# BPM.net
KiCad netlist of a schematic drawn in EAGLE
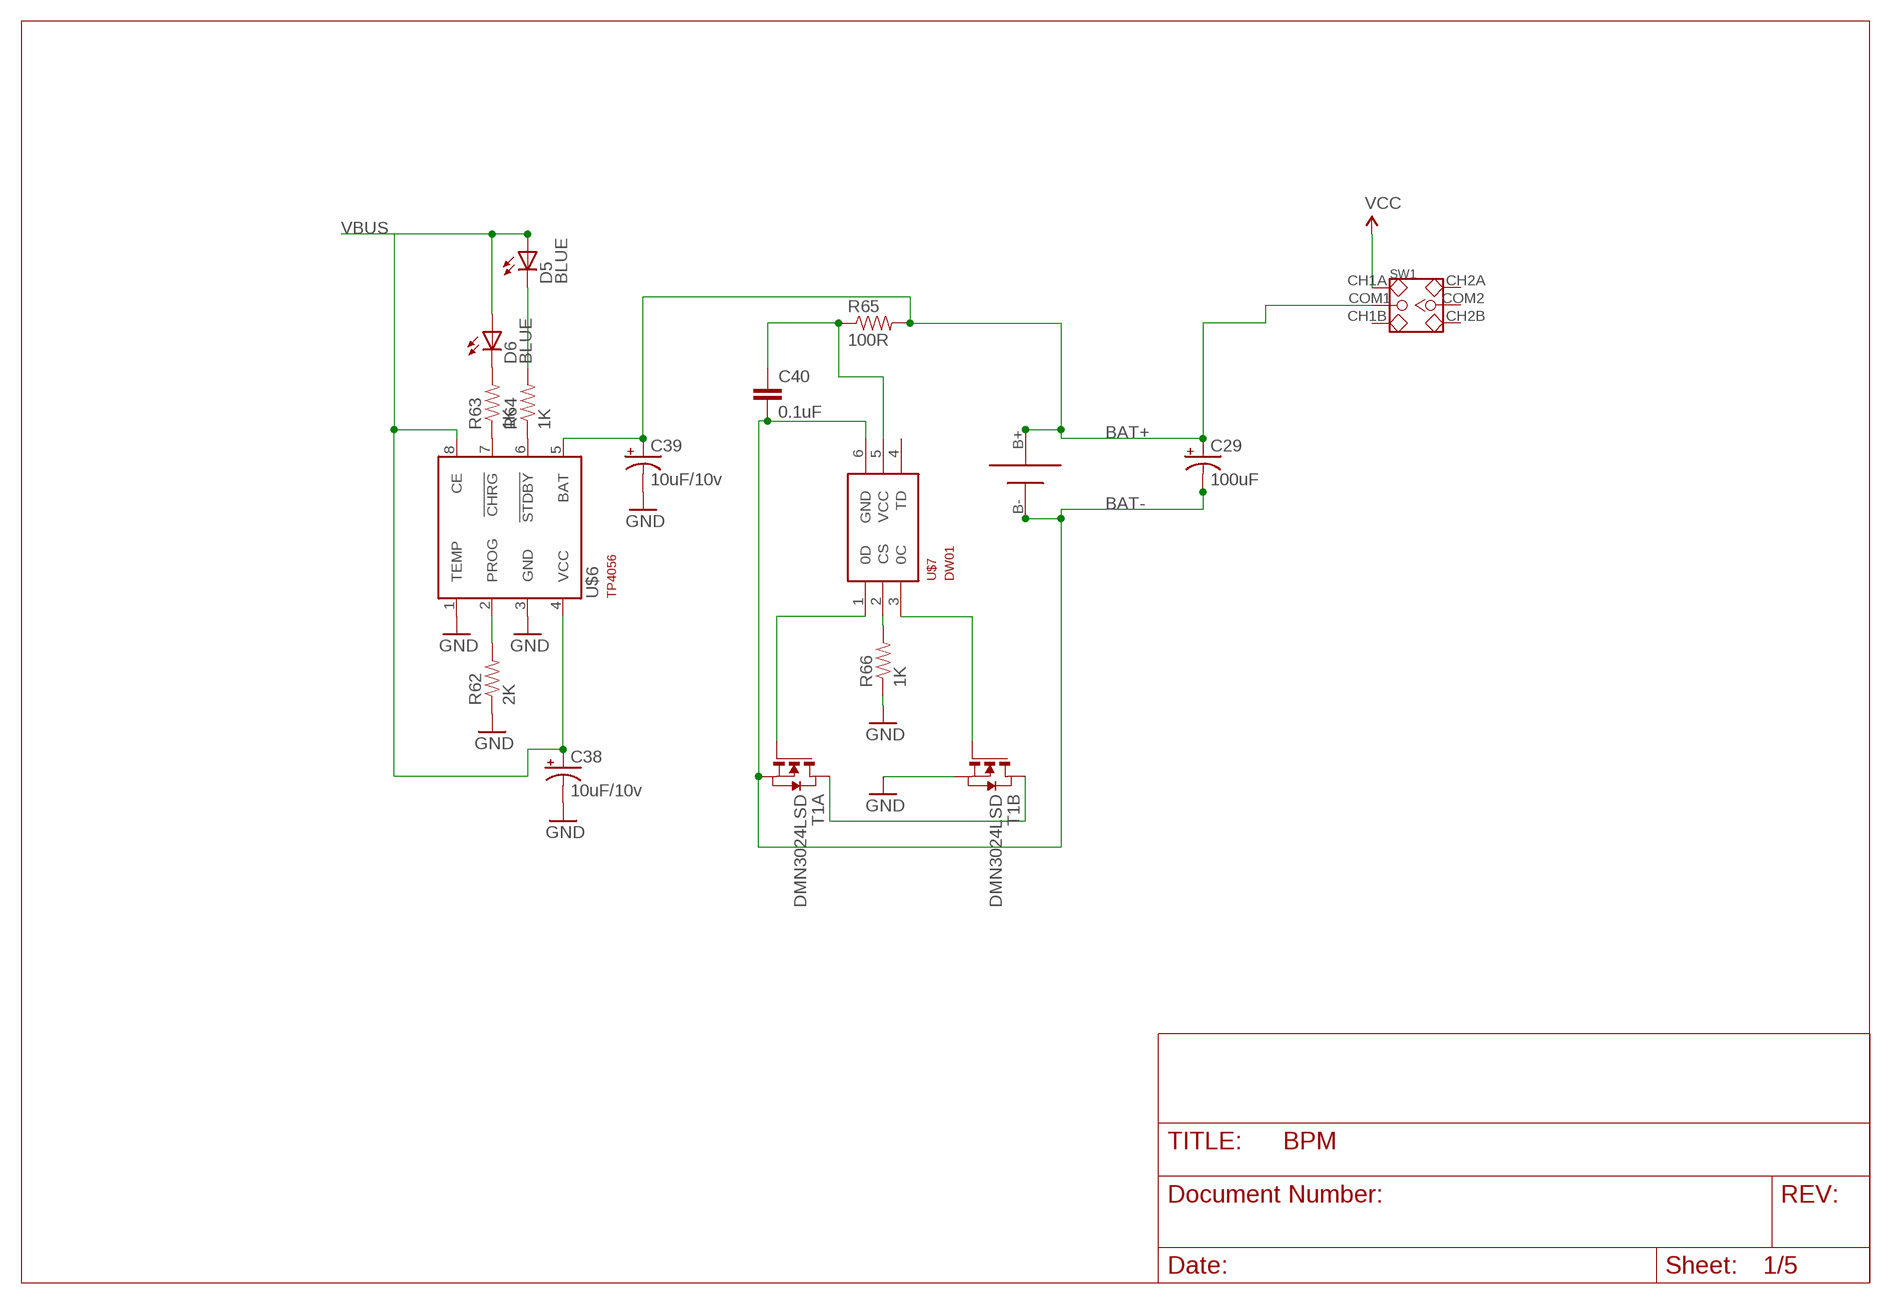
[diagram p0: schematic, sheet 1]
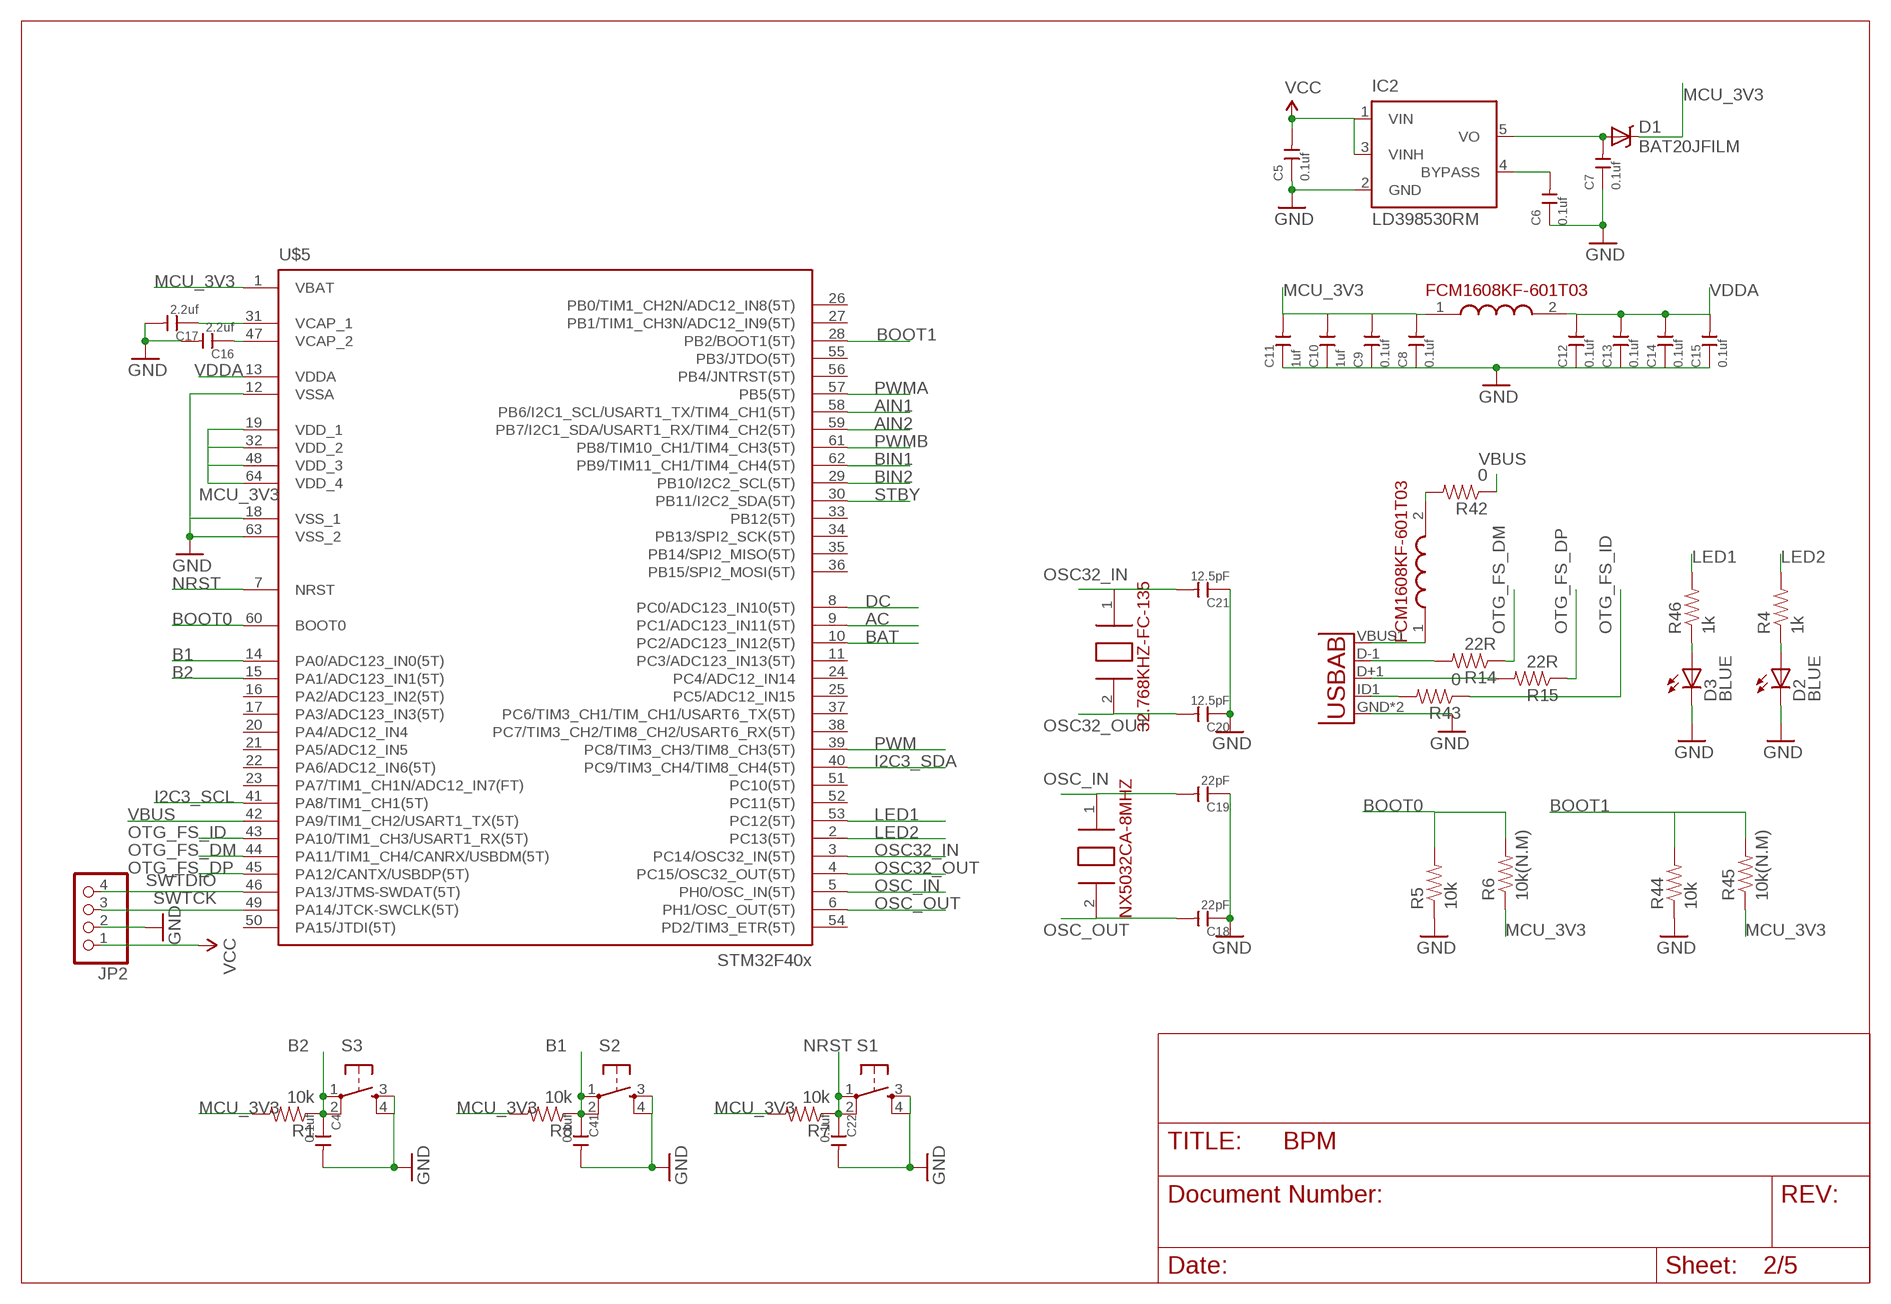
[diagram p1: schematic, sheet 2]
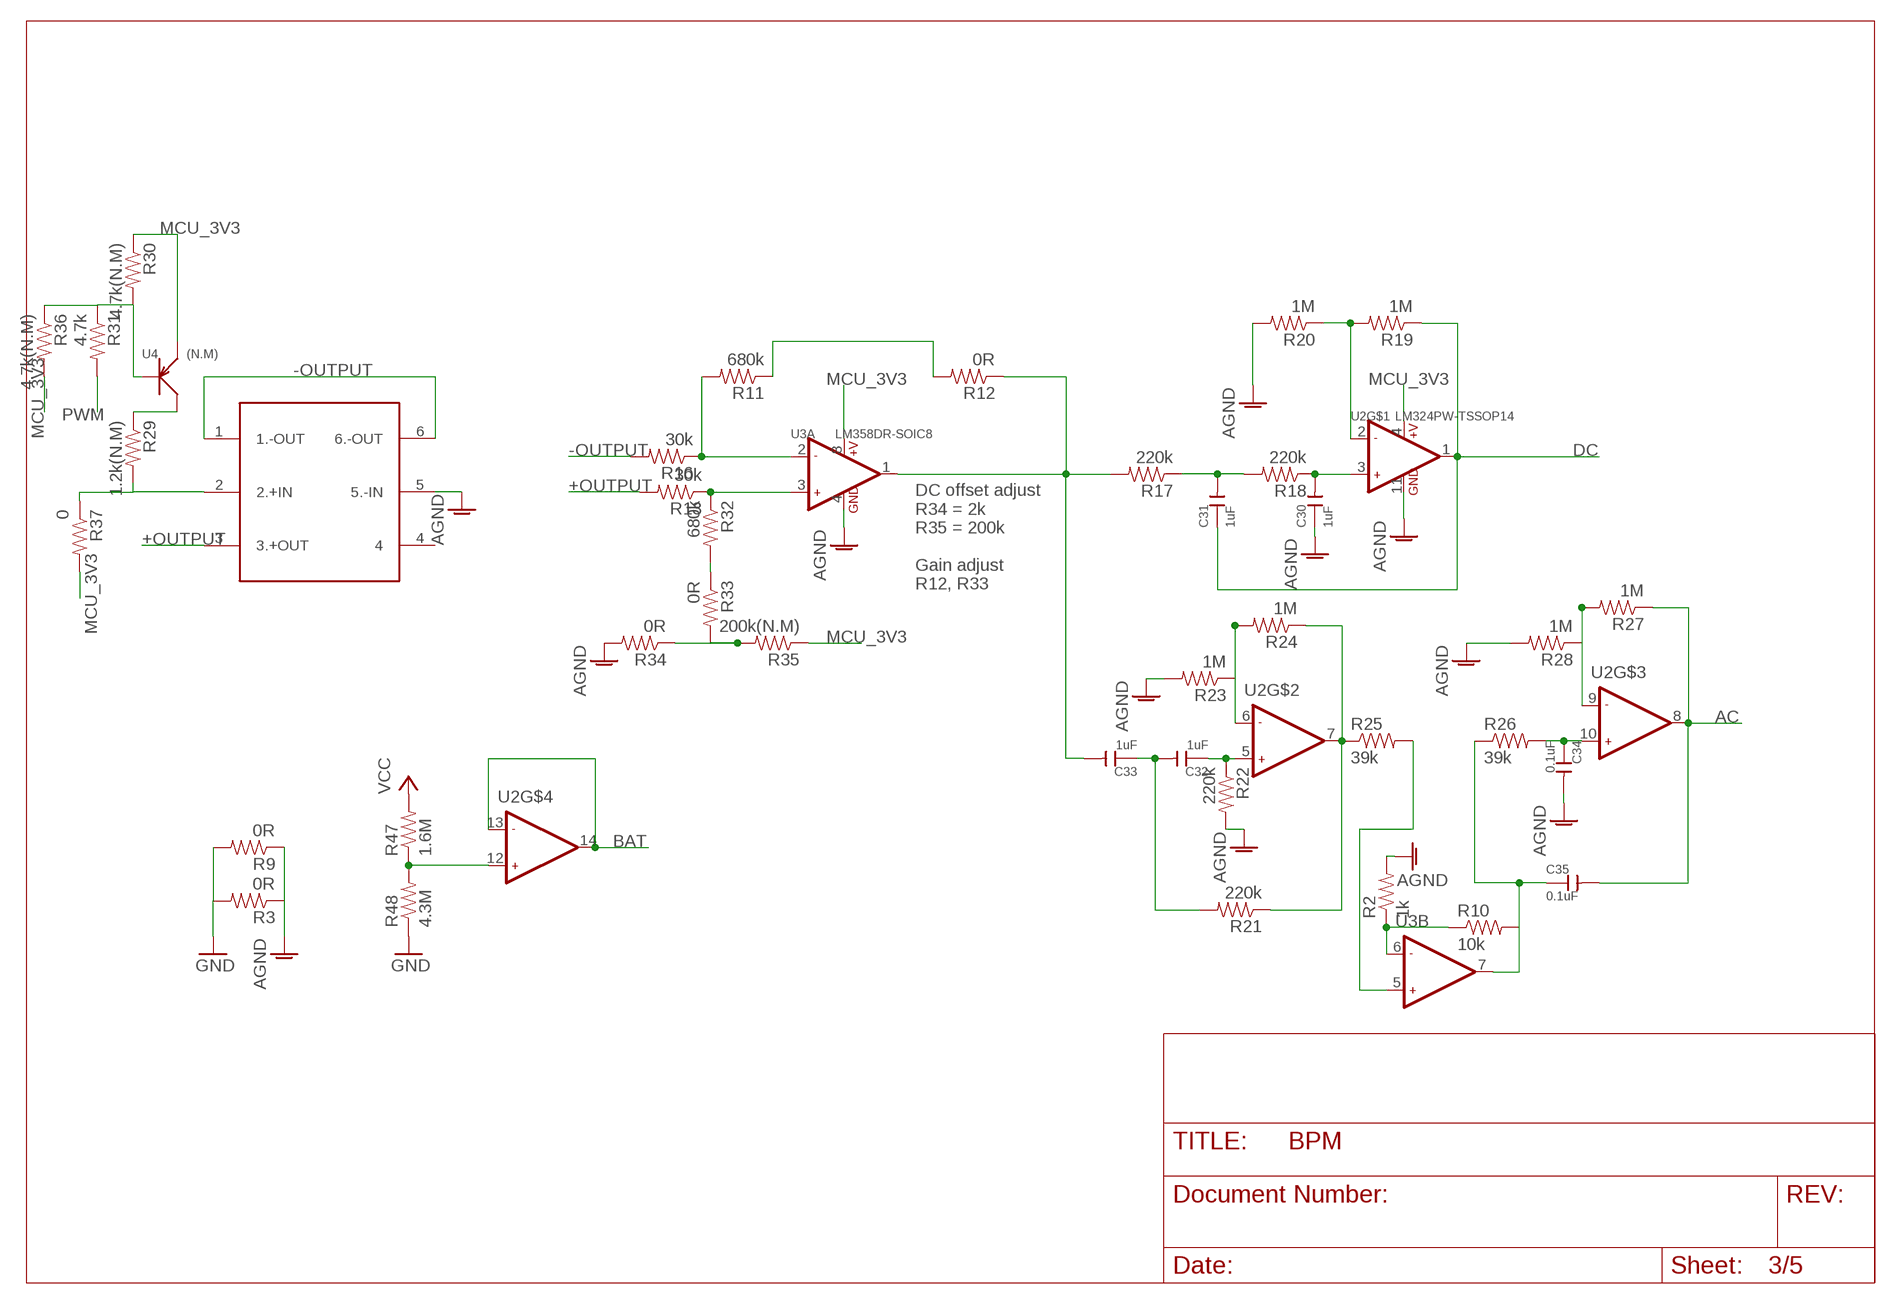
[diagram p2: schematic, sheet 3]
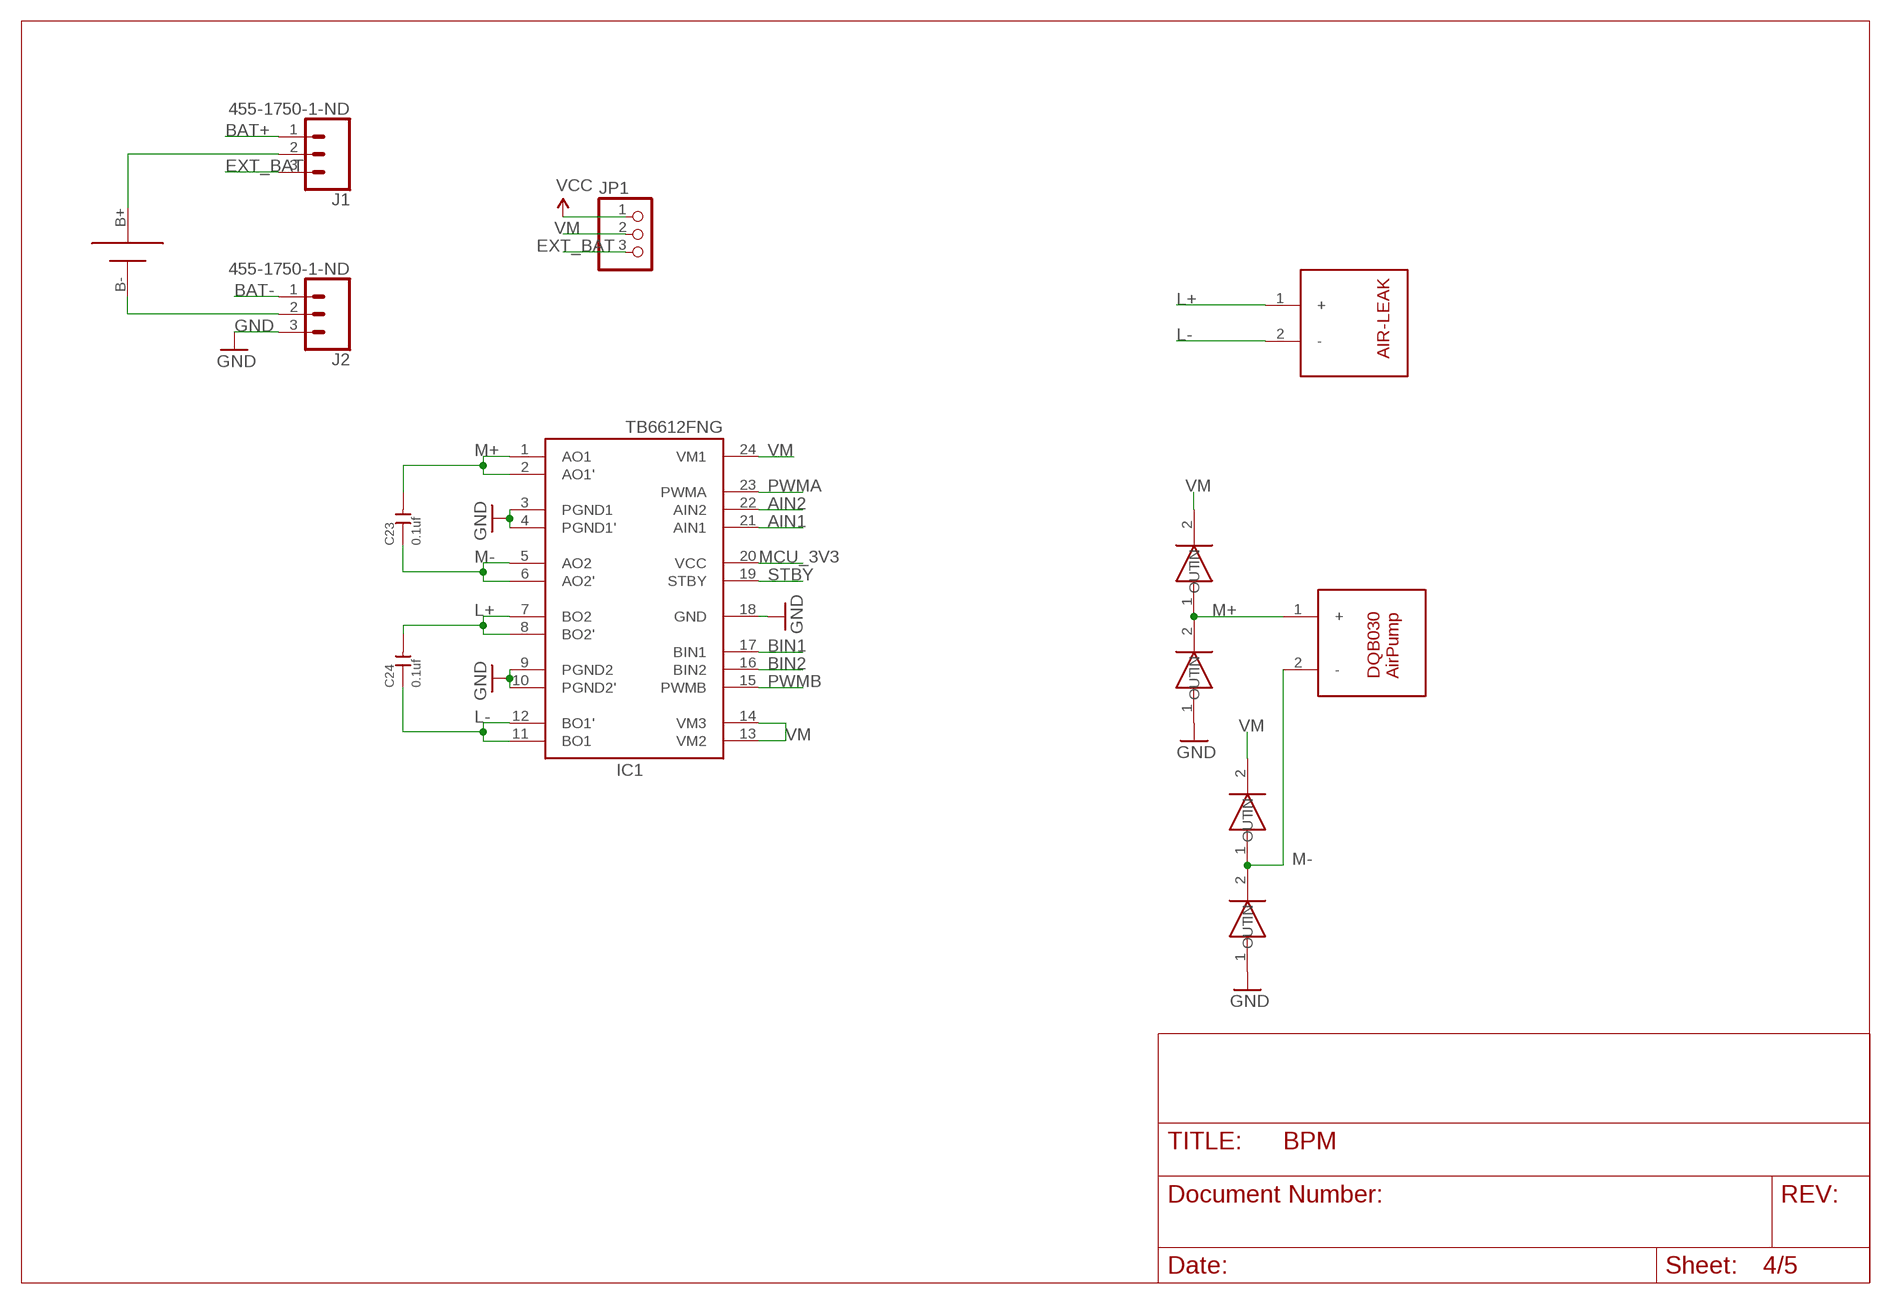
[diagram p3: schematic, sheet 4]
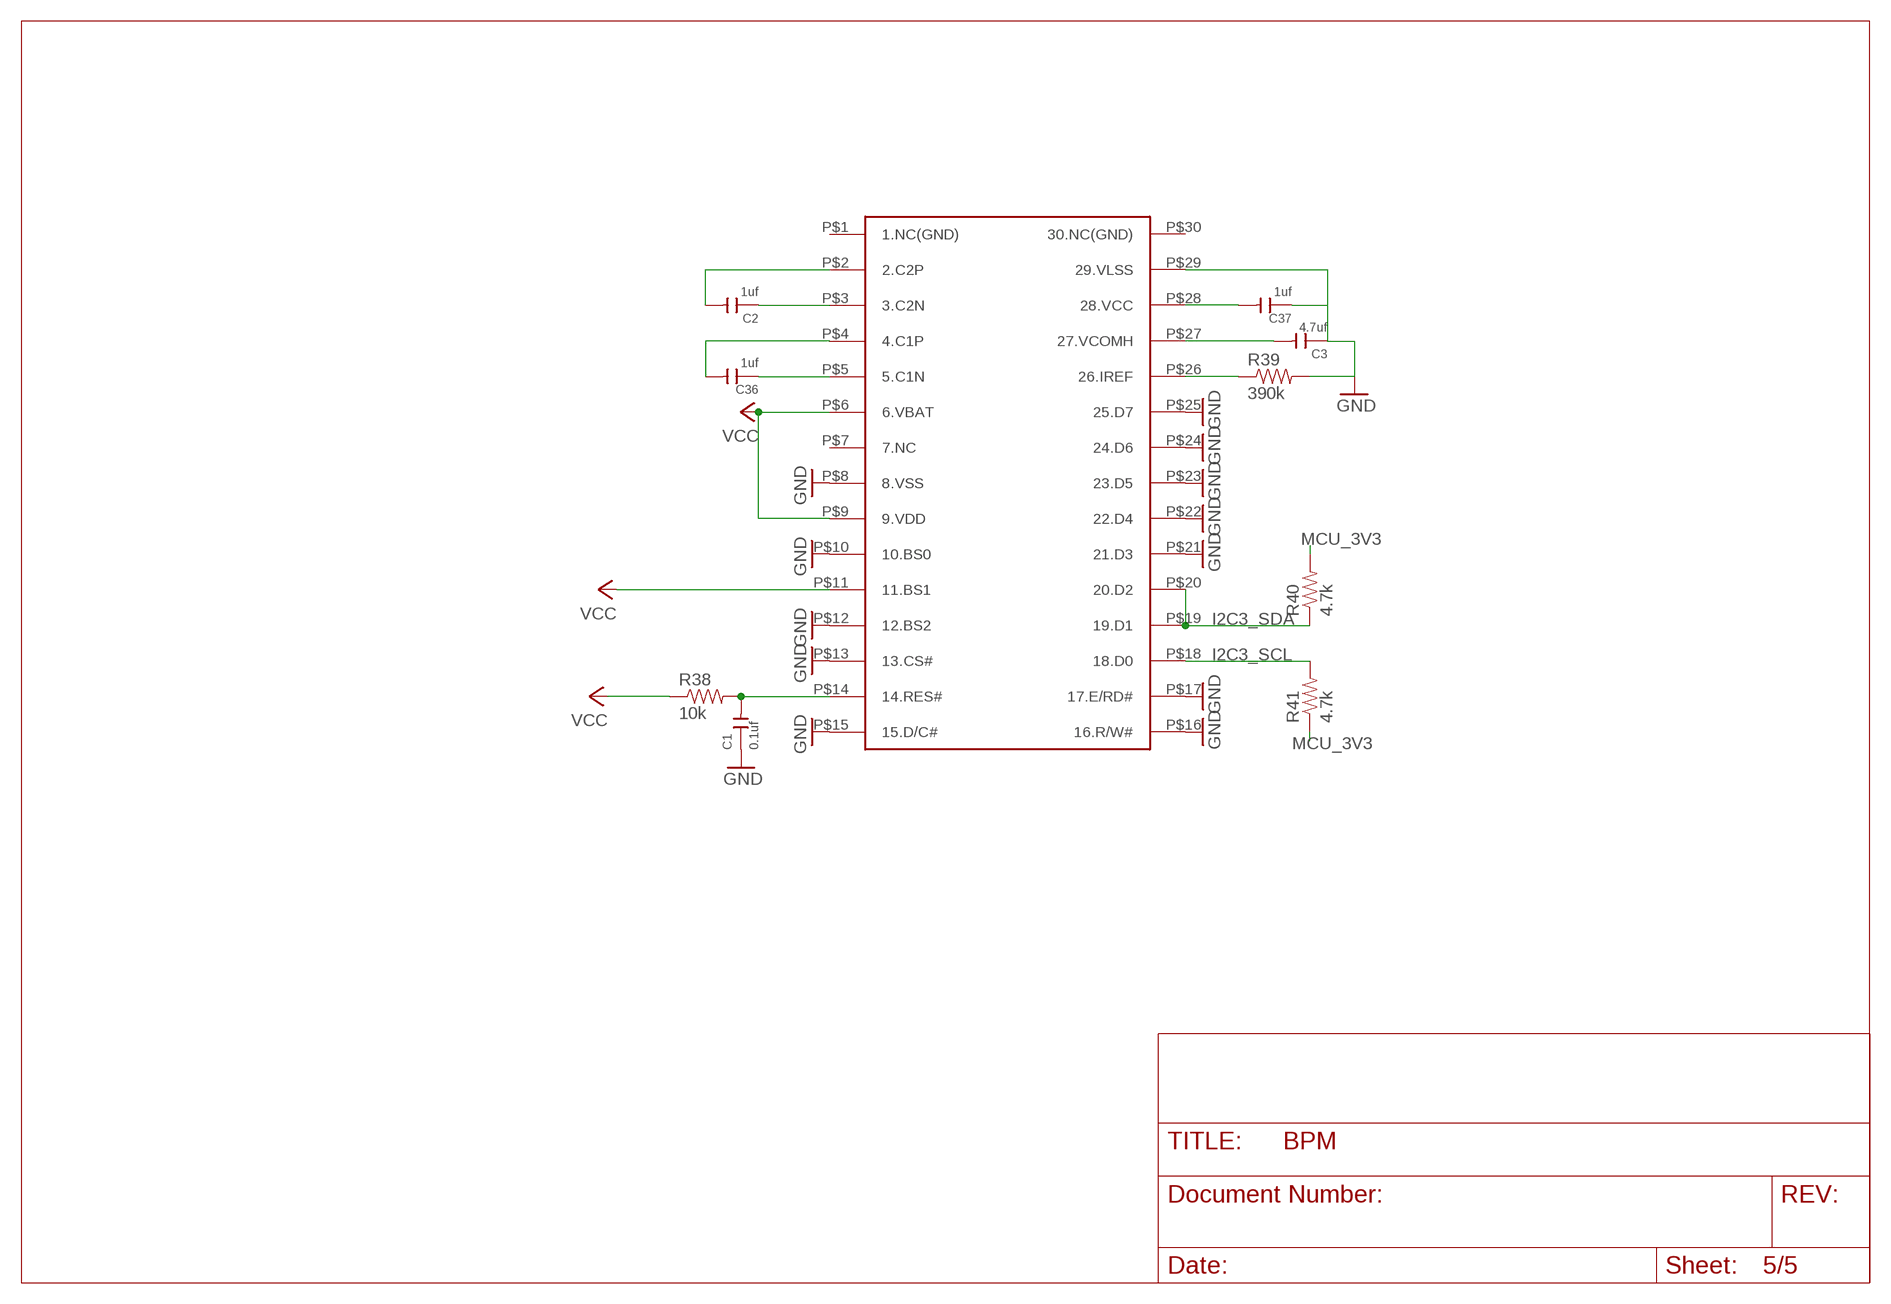
[diagram p4: schematic, sheet 5]

(export (version "E")
  (design (tool "Eeschema 10.0.6"))
  (components
    (comp (ref "C4")
      (value "0.1uf")
      (footprint "eagle-import:C0603")
      (fields (field (name "MPN") "CC0603KRX5R6BB475"))
      (libsource (lib "eagle-import") (part "CERAMIC-4.7UF-10V-10%-X5R(0603)"))
    )
    (comp (ref "C5")
      (value "0.1uf")
      (footprint "eagle-import:C0603")
      (fields (field (name "MPN") "CC0603KRX5R6BB475"))
      (libsource (lib "eagle-import") (part "CERAMIC-4.7UF-10V-10%-X5R(0603)"))
    )
    (comp (ref "C6")
      (value "0.1uf")
      (footprint "eagle-import:C0603")
      (fields (field (name "MPN") "CC0603KRX5R6BB475"))
      (libsource (lib "eagle-import") (part "CERAMIC-4.7UF-10V-10%-X5R(0603)"))
    )
    (comp (ref "C7")
      (value "0.1uf")
      (footprint "eagle-import:C0603")
      (fields (field (name "MPN") "CC0603KRX5R6BB475"))
      (libsource (lib "eagle-import") (part "CERAMIC-4.7UF-10V-10%-X5R(0603)"))
    )
    (comp (ref "C8")
      (value "0.1uf")
      (footprint "eagle-import:C0603")
      (fields (field (name "MPN") "CC0603KRX5R6BB475"))
      (libsource (lib "eagle-import") (part "CERAMIC-4.7UF-10V-10%-X5R(0603)"))
    )
    (comp (ref "C9")
      (value "0.1uf")
      (footprint "eagle-import:C0603")
      (fields (field (name "MPN") "CC0603KRX5R6BB475"))
      (libsource (lib "eagle-import") (part "CERAMIC-4.7UF-10V-10%-X5R(0603)"))
    )
    (comp (ref "C10")
      (value "1uf")
      (footprint "eagle-import:C0603")
      (fields (field (name "MPN") "CC0603KRX5R6BB475"))
      (libsource (lib "eagle-import") (part "CERAMIC-4.7UF-10V-10%-X5R(0603)"))
    )
    (comp (ref "C11")
      (value "1uf")
      (footprint "eagle-import:C0603")
      (fields (field (name "MPN") "CC0603KRX5R6BB475"))
      (libsource (lib "eagle-import") (part "CERAMIC-4.7UF-10V-10%-X5R(0603)"))
    )
    (comp (ref "C12")
      (value "0.1uf")
      (footprint "eagle-import:C0603")
      (fields (field (name "MPN") "CC0603KRX5R6BB475"))
      (libsource (lib "eagle-import") (part "CERAMIC-4.7UF-10V-10%-X5R(0603)"))
    )
    (comp (ref "C13")
      (value "0.1uf")
      (footprint "eagle-import:C0603")
      (fields (field (name "MPN") "CC0603KRX5R6BB475"))
      (libsource (lib "eagle-import") (part "CERAMIC-4.7UF-10V-10%-X5R(0603)"))
    )
    (comp (ref "C14")
      (value "0.1uf")
      (footprint "eagle-import:C0603")
      (fields (field (name "MPN") "CC0603KRX5R6BB475"))
      (libsource (lib "eagle-import") (part "CERAMIC-4.7UF-10V-10%-X5R(0603)"))
    )
    (comp (ref "C15")
      (value "0.1uf")
      (footprint "eagle-import:C0603")
      (fields (field (name "MPN") "CC0603KRX5R6BB475"))
      (libsource (lib "eagle-import") (part "CERAMIC-4.7UF-10V-10%-X5R(0603)"))
    )
    (comp (ref "C16")
      (value "2.2uf")
      (footprint "eagle-import:C0603")
      (fields (field (name "MPN") "CC0603KRX5R6BB475"))
      (libsource (lib "eagle-import") (part "CERAMIC-4.7UF-10V-10%-X5R(0603)"))
    )
    (comp (ref "C17")
      (value "2.2uf")
      (footprint "eagle-import:C0603")
      (fields (field (name "MPN") "CC0603KRX5R6BB475"))
      (libsource (lib "eagle-import") (part "CERAMIC-4.7UF-10V-10%-X5R(0603)"))
    )
    (comp (ref "C18")
      (value "22pF")
      (footprint "eagle-import:C0603")
      (fields (field (name "MPN") "CC0603KRX5R6BB475"))
      (libsource (lib "eagle-import") (part "CERAMIC-4.7UF-10V-10%-X5R(0603)"))
    )
    (comp (ref "C19")
      (value "22pF")
      (footprint "eagle-import:C0603")
      (fields (field (name "MPN") "CC0603KRX5R6BB475"))
      (libsource (lib "eagle-import") (part "CERAMIC-4.7UF-10V-10%-X5R(0603)"))
    )
    (comp (ref "C20")
      (value "12.5pF")
      (footprint "eagle-import:C0603")
      (fields (field (name "MPN") "CC0603KRX5R6BB475"))
      (libsource (lib "eagle-import") (part "CERAMIC-4.7UF-10V-10%-X5R(0603)"))
    )
    (comp (ref "C21")
      (value "12.5pF")
      (footprint "eagle-import:C0603")
      (fields (field (name "MPN") "CC0603KRX5R6BB475"))
      (libsource (lib "eagle-import") (part "CERAMIC-4.7UF-10V-10%-X5R(0603)"))
    )
    (comp (ref "C22")
      (value "0.1uf")
      (footprint "eagle-import:C0603")
      (fields (field (name "MPN") "CC0603KRX5R6BB475"))
      (libsource (lib "eagle-import") (part "CERAMIC-4.7UF-10V-10%-X5R(0603)"))
    )
    (comp (ref "C41")
      (value "0.1uf")
      (footprint "eagle-import:C0603")
      (fields (field (name "MPN") "CC0603KRX5R6BB475"))
      (libsource (lib "eagle-import") (part "CERAMIC-4.7UF-10V-10%-X5R(0603)"))
    )
    (comp (ref "D1")
      (value "BAT20JFILM")
      (footprint "eagle-import:SOD-323")
      (libsource (lib "eagle-import") (part "BAT20JFILM"))
    )
    (comp (ref "D2")
      (value "BLUE")
      (footprint "eagle-import:LED-0603")
      (libsource (lib "eagle-import") (part "LED-BLUE0603"))
    )
    (comp (ref "D3")
      (value "BLUE")
      (footprint "eagle-import:LED-0603")
      (libsource (lib "eagle-import") (part "LED-BLUE0603"))
    )
    (comp (ref "IC2")
      (value "LD398530RM")
      (footprint "eagle-import:SOT23-5L")
      (libsource (lib "eagle-import") (part "LD3985M30R"))
    )
    (comp (ref "JP2")
      (value "PINHD-1X4")
      (footprint "eagle-import:1X04")
      (libsource (lib "eagle-import") (part "PINHD-1X4"))
    )
    (comp (ref "R1")
      (value "10k")
      (footprint "eagle-import:0603")
      (libsource (lib "eagle-import") (part "0OHM1/10W5%(0603)"))
    )
    (comp (ref "R4")
      (value "1k")
      (footprint "eagle-import:0603")
      (libsource (lib "eagle-import") (part "0OHM1/10W5%(0603)"))
    )
    (comp (ref "R5")
      (value "10k")
      (footprint "eagle-import:0603")
      (libsource (lib "eagle-import") (part "0OHM1/10W5%(0603)"))
    )
    (comp (ref "R6")
      (value "10k(N.M)")
      (footprint "eagle-import:0603")
      (libsource (lib "eagle-import") (part "0OHM1/10W5%(0603)"))
    )
    (comp (ref "R7")
      (value "10k")
      (footprint "eagle-import:0603")
      (libsource (lib "eagle-import") (part "0OHM1/10W5%(0603)"))
    )
    (comp (ref "R8")
      (value "10k")
      (footprint "eagle-import:0603")
      (libsource (lib "eagle-import") (part "0OHM1/10W5%(0603)"))
    )
    (comp (ref "R14")
      (value "22R")
      (footprint "eagle-import:0603-RES")
      (libsource (lib "eagle-import") (part "390OHM1/10W1%(0603)"))
    )
    (comp (ref "R15")
      (value "22R")
      (footprint "eagle-import:0603-RES")
      (libsource (lib "eagle-import") (part "390OHM1/10W1%(0603)"))
    )
    (comp (ref "R42")
      (value "0")
      (footprint "eagle-import:0603-RES")
      (libsource (lib "eagle-import") (part "390OHM1/10W1%(0603)"))
    )
    (comp (ref "R43")
      (value "0")
      (footprint "eagle-import:0603-RES")
      (libsource (lib "eagle-import") (part "390OHM1/10W1%(0603)"))
    )
    (comp (ref "R44")
      (value "10k")
      (footprint "eagle-import:0603")
      (libsource (lib "eagle-import") (part "0OHM1/10W5%(0603)"))
    )
    (comp (ref "R45")
      (value "10k(N.M)")
      (footprint "eagle-import:0603")
      (libsource (lib "eagle-import") (part "0OHM1/10W5%(0603)"))
    )
    (comp (ref "R46")
      (value "1k")
      (footprint "eagle-import:0603")
      (libsource (lib "eagle-import") (part "0OHM1/10W5%(0603)"))
    )
    (comp (ref "S1")
      (value "TAC_SWITCHSMD")
      (footprint "eagle-import:TACTILE_SWITCH_SMD")
      (libsource (lib "eagle-import") (part "TAC_SWITCHSMD"))
    )
    (comp (ref "S2")
      (value "TAC_SWITCHSMD")
      (footprint "eagle-import:TACTILE_SWITCH_SMD")
      (libsource (lib "eagle-import") (part "TAC_SWITCHSMD"))
    )
    (comp (ref "S3")
      (value "TAC_SWITCHSMD")
      (footprint "eagle-import:TACTILE_SWITCH_SMD")
      (libsource (lib "eagle-import") (part "TAC_SWITCHSMD"))
    )
    (comp (ref "U$5")
      (value "STM32F405R")
      (footprint "eagle-import:TQFP64")
      (libsource (lib "eagle-import") (part "STM32F405R"))
    )
    (comp (ref "U$8")
      (value "32.768KHZ-FC-135")
      (footprint "eagle-import:32.768KHZ-FC-135")
      (libsource (lib "eagle-import") (part "32.768KHZ-FC-135"))
    )
    (comp (ref "U$9")
      (value "NX5032CA-8MHZ")
      (footprint "eagle-import:NX5032CA-8MHZ")
      (libsource (lib "eagle-import") (part "NX5032CA-8MHZ"))
    )
    (comp (ref "U$10")
      (value "FCM1608KF-601T03")
      (footprint "eagle-import:FCM1608KF-601T03")
      (libsource (lib "eagle-import") (part "FCM1608KF-601T03"))
    )
    (comp (ref "U$15")
      (value "FCM1608KF-601T03")
      (footprint "eagle-import:FCM1608KF-601T03")
      (libsource (lib "eagle-import") (part "FCM1608KF-601T03"))
    )
    (comp (ref "U1")
      (value "USB\"\"")
      (footprint "eagle-import:USB-MICRO-SMD")
      (libsource (lib "eagle-import") (part "USB{dblquote}{dblquote}"))
    )
    (comp (ref "C29")
      (value "100uF")
      (footprint "eagle-import:NIPPON_F80")
      (libsource (lib "eagle-import") (part "CAP_POLF80"))
    )
    (comp (ref "C38")
      (value "10uF/10v")
      (footprint "eagle-import:EIA3216-KIT")
      (libsource (lib "eagle-import") (part "CAP_POL1206-KIT"))
    )
    (comp (ref "C39")
      (value "10uF/10v")
      (footprint "eagle-import:EIA3216-KIT")
      (libsource (lib "eagle-import") (part "CAP_POL1206-KIT"))
    )
    (comp (ref "C40")
      (value "0.1uF")
      (footprint "eagle-import:0603-CAP")
      (libsource (lib "eagle-import") (part "0.1UF-100V-10%(0603)"))
    )
    (comp (ref "D5")
      (value "BLUE")
      (footprint "eagle-import:LED-0603")
      (libsource (lib "eagle-import") (part "LED-BLUE0603"))
    )
    (comp (ref "D6")
      (value "BLUE")
      (footprint "eagle-import:LED-0603")
      (libsource (lib "eagle-import") (part "LED-BLUE0603"))
    )
    (comp (ref "R62")
      (value "2K")
      (footprint "eagle-import:0603-RES")
      (libsource (lib "eagle-import") (part "1KOHM1/10W1%(0603)"))
    )
    (comp (ref "R63")
      (value "1K")
      (footprint "eagle-import:0603-RES")
      (libsource (lib "eagle-import") (part "1KOHM1/10W1%(0603)"))
    )
    (comp (ref "R64")
      (value "1K")
      (footprint "eagle-import:0603-RES")
      (libsource (lib "eagle-import") (part "1KOHM1/10W1%(0603)"))
    )
    (comp (ref "R65")
      (value "100R")
      (footprint "eagle-import:0603-RES")
      (libsource (lib "eagle-import") (part "1KOHM1/10W1%(0603)"))
    )
    (comp (ref "R66")
      (value "1K")
      (footprint "eagle-import:0603-RES")
      (libsource (lib "eagle-import") (part "1KOHM1/10W1%(0603)"))
    )
    (comp (ref "SW1")
      (value "SMD-TOGGLE-SWITCH-2CH(2X3P-7X3.5MM)")
      (footprint "eagle-import:SW6-2.54-SMD-7.0X3.5X1.5MM")
      (libsource (lib "eagle-import") (part "SMD-TOGGLE-SWITCH-2CH(2X3P-7X3.5MM)"))
    )
    (comp (ref "T1")
      (value "DMN3024LSD")
      (footprint "eagle-import:TSSOP-8")
      (libsource (lib "eagle-import") (part "DMN3024LSD"))
    )
    (comp (ref "U$4")
      (value "18650SMD")
      (footprint "eagle-import:18650SMD")
      (libsource (lib "eagle-import") (part "18650SMD"))
    )
    (comp (ref "U$6")
      (value "TP4056")
      (footprint "eagle-import:SOT23-8")
      (libsource (lib "eagle-import") (part "TP4056"))
    )
    (comp (ref "U$7")
      (value "DW01")
      (footprint "eagle-import:SOT23-6")
      (libsource (lib "eagle-import") (part "DW01"))
    )
    (comp (ref "C30")
      (value "1uF")
      (footprint "eagle-import:C0603")
      (fields (field (name "MPN") "CC0603KRX5R6BB475"))
      (libsource (lib "eagle-import") (part "CERAMIC-4.7UF-10V-10%-X5R(0603)"))
    )
    (comp (ref "C31")
      (value "1uF")
      (footprint "eagle-import:C0603")
      (fields (field (name "MPN") "CC0603KRX5R6BB475"))
      (libsource (lib "eagle-import") (part "CERAMIC-4.7UF-10V-10%-X5R(0603)"))
    )
    (comp (ref "C32")
      (value "1uF")
      (footprint "eagle-import:C0603")
      (fields (field (name "MPN") "CC0603KRX5R6BB475"))
      (libsource (lib "eagle-import") (part "CERAMIC-4.7UF-10V-10%-X5R(0603)"))
    )
    (comp (ref "C33")
      (value "1uF")
      (footprint "eagle-import:C0603")
      (fields (field (name "MPN") "CC0603KRX5R6BB475"))
      (libsource (lib "eagle-import") (part "CERAMIC-4.7UF-10V-10%-X5R(0603)"))
    )
    (comp (ref "C34")
      (value "0.1uF")
      (footprint "eagle-import:C0603")
      (fields (field (name "MPN") "CC0603KRX5R6BB475"))
      (libsource (lib "eagle-import") (part "CERAMIC-4.7UF-10V-10%-X5R(0603)"))
    )
    (comp (ref "C35")
      (value "0.1uF")
      (footprint "eagle-import:C0603")
      (fields (field (name "MPN") "CC0603KRX5R6BB475"))
      (libsource (lib "eagle-import") (part "CERAMIC-4.7UF-10V-10%-X5R(0603)"))
    )
    (comp (ref "R2")
      (value "1k")
      (footprint "eagle-import:0603")
      (libsource (lib "eagle-import") (part "0OHM1/10W5%(0603)"))
    )
    (comp (ref "R3")
      (value "0R")
      (footprint "eagle-import:0603")
      (libsource (lib "eagle-import") (part "0OHM1/10W5%(0603)"))
    )
    (comp (ref "R9")
      (value "0R")
      (footprint "eagle-import:0603")
      (libsource (lib "eagle-import") (part "0OHM1/10W5%(0603)"))
    )
    (comp (ref "R10")
      (value "10k")
      (footprint "eagle-import:0603")
      (libsource (lib "eagle-import") (part "0OHM1/10W5%(0603)"))
    )
    (comp (ref "R11")
      (value "680k")
      (footprint "eagle-import:0603")
      (libsource (lib "eagle-import") (part "0OHM1/10W5%(0603)"))
    )
    (comp (ref "R12")
      (value "0R")
      (footprint "eagle-import:0603")
      (libsource (lib "eagle-import") (part "0OHM1/10W5%(0603)"))
    )
    (comp (ref "R13")
      (value "30k")
      (footprint "eagle-import:0603")
      (libsource (lib "eagle-import") (part "0OHM1/10W5%(0603)"))
    )
    (comp (ref "R16")
      (value "30k")
      (footprint "eagle-import:0603")
      (libsource (lib "eagle-import") (part "0OHM1/10W5%(0603)"))
    )
    (comp (ref "R17")
      (value "220k")
      (footprint "eagle-import:0603")
      (libsource (lib "eagle-import") (part "0OHM1/10W5%(0603)"))
    )
    (comp (ref "R18")
      (value "220k")
      (footprint "eagle-import:0603")
      (libsource (lib "eagle-import") (part "0OHM1/10W5%(0603)"))
    )
    (comp (ref "R19")
      (value "1M")
      (footprint "eagle-import:0603")
      (libsource (lib "eagle-import") (part "0OHM1/10W5%(0603)"))
    )
    (comp (ref "R20")
      (value "1M")
      (footprint "eagle-import:0603")
      (libsource (lib "eagle-import") (part "0OHM1/10W5%(0603)"))
    )
    (comp (ref "R21")
      (value "220k")
      (footprint "eagle-import:0603")
      (libsource (lib "eagle-import") (part "0OHM1/10W5%(0603)"))
    )
    (comp (ref "R22")
      (value "220k")
      (footprint "eagle-import:0603")
      (libsource (lib "eagle-import") (part "0OHM1/10W5%(0603)"))
    )
    (comp (ref "R23")
      (value "1M")
      (footprint "eagle-import:0603")
      (libsource (lib "eagle-import") (part "0OHM1/10W5%(0603)"))
    )
    (comp (ref "R24")
      (value "1M")
      (footprint "eagle-import:0603")
      (libsource (lib "eagle-import") (part "0OHM1/10W5%(0603)"))
    )
    (comp (ref "R25")
      (value "39k")
      (footprint "eagle-import:0603")
      (libsource (lib "eagle-import") (part "0OHM1/10W5%(0603)"))
    )
    (comp (ref "R26")
      (value "39k")
      (footprint "eagle-import:0603")
      (libsource (lib "eagle-import") (part "0OHM1/10W5%(0603)"))
    )
    (comp (ref "R27")
      (value "1M")
      (footprint "eagle-import:0603")
      (libsource (lib "eagle-import") (part "0OHM1/10W5%(0603)"))
    )
    (comp (ref "R28")
      (value "1M")
      (footprint "eagle-import:0603")
      (libsource (lib "eagle-import") (part "0OHM1/10W5%(0603)"))
    )
    (comp (ref "R29")
      (value "1.2k(N.M)")
      (footprint "eagle-import:0603")
      (libsource (lib "eagle-import") (part "0OHM1/10W5%(0603)"))
    )
    (comp (ref "R30")
      (value "4.7k(N.M)")
      (footprint "eagle-import:0603")
      (libsource (lib "eagle-import") (part "0OHM1/10W5%(0603)"))
    )
    (comp (ref "R31")
      (value "4.7k")
      (footprint "eagle-import:0603")
      (libsource (lib "eagle-import") (part "0OHM1/10W5%(0603)"))
    )
    (comp (ref "R32")
      (value "680k")
      (footprint "eagle-import:0603")
      (libsource (lib "eagle-import") (part "0OHM1/10W5%(0603)"))
    )
    (comp (ref "R33")
      (value "0R")
      (footprint "eagle-import:0603")
      (libsource (lib "eagle-import") (part "0OHM1/10W5%(0603)"))
    )
    (comp (ref "R34")
      (value "0R")
      (footprint "eagle-import:0603")
      (libsource (lib "eagle-import") (part "0OHM1/10W5%(0603)"))
    )
    (comp (ref "R35")
      (value "200k(N.M)")
      (footprint "eagle-import:0603")
      (libsource (lib "eagle-import") (part "0OHM1/10W5%(0603)"))
    )
    (comp (ref "R36")
      (value "4.7k(N.M)")
      (footprint "eagle-import:0603")
      (libsource (lib "eagle-import") (part "0OHM1/10W5%(0603)"))
    )
    (comp (ref "R37")
      (value "0")
      (footprint "eagle-import:0603")
      (libsource (lib "eagle-import") (part "0OHM1/10W5%(0603)"))
    )
    (comp (ref "R47")
      (value "1.6M")
      (footprint "eagle-import:0603")
      (libsource (lib "eagle-import") (part "0OHM1/10W5%(0603)"))
    )
    (comp (ref "R48")
      (value "4.3M")
      (footprint "eagle-import:0603")
      (libsource (lib "eagle-import") (part "0OHM1/10W5%(0603)"))
    )
    (comp (ref "U$1")
      (value "MPS-3117-006G")
      (footprint "eagle-import:MPS-3117-006G")
      (libsource (lib "eagle-import") (part "MPS-3117-006G"))
    )
    (comp (ref "U2")
      (value "LM324PW-TSSOP14")
      (footprint "eagle-import:TSSOP14-0.65-5X4.4MM")
      (fields (field (name "MPN") "LM324PW"))
      (libsource (lib "eagle-import") (part "AMPLIFIER-LM324PW(TSSOP14)"))
    )
    (comp (ref "U3")
      (value "LM358DR-SOIC8")
      (footprint "eagle-import:SOIC8-1.27-5X4MM")
      (fields (field (name "MPN") "LM358DR"))
      (libsource (lib "eagle-import") (part "AMPLIFIER-LM358DR(SOIC8)"))
    )
    (comp (ref "U4")
      (value "(N.M)")
      (footprint "eagle-import:SOT-23")
      (libsource (lib "eagle-import") (part "TRANSISTOR-PNP"))
    )
    (comp (ref "C23")
      (value "0.1uf")
      (footprint "eagle-import:C0603")
      (fields (field (name "MPN") "CC0603KRX5R6BB475"))
      (libsource (lib "eagle-import") (part "CERAMIC-4.7UF-10V-10%-X5R(0603)"))
    )
    (comp (ref "C24")
      (value "0.1uf")
      (footprint "eagle-import:C0603")
      (fields (field (name "MPN") "CC0603KRX5R6BB475"))
      (libsource (lib "eagle-import") (part "CERAMIC-4.7UF-10V-10%-X5R(0603)"))
    )
    (comp (ref "IC1")
      (value "TB6612FNG")
      (footprint "eagle-import:SSOP24")
      (libsource (lib "eagle-import") (part "TB6612FNG"))
    )
    (comp (ref "J1")
      (value "455-1750-1-ND")
      (footprint "eagle-import:1X03")
      (libsource (lib "eagle-import") (part "CONN_03"))
    )
    (comp (ref "J2")
      (value "455-1750-1-ND")
      (footprint "eagle-import:1X03")
      (libsource (lib "eagle-import") (part "CONN_03"))
    )
    (comp (ref "JP1")
      (value "PINHD-1X3")
      (footprint "eagle-import:1X03")
      (libsource (lib "eagle-import") (part "PINHD-1X3"))
    )
    (comp (ref "U$11")
      (value "AIR-LEAK")
      (footprint "eagle-import:AIR-LEAK")
      (libsource (lib "eagle-import") (part "AIR-LEAK"))
    )
    (comp (ref "U$12")
      (value "DQB030-AIRPUMP")
      (footprint "eagle-import:DQB030-AIRPUMP")
      (libsource (lib "eagle-import") (part "DQB030-AIRPUMP"))
    )
    (comp (ref "U$13")
      (value "SMA-SS34")
      (footprint "eagle-import:SMA-SS34")
      (libsource (lib "eagle-import") (part "SMA-SS34"))
    )
    (comp (ref "U$14")
      (value "SMA-SS34")
      (footprint "eagle-import:SMA-SS34")
      (libsource (lib "eagle-import") (part "SMA-SS34"))
    )
    (comp (ref "U$16")
      (value "SMA-SS34")
      (footprint "eagle-import:SMA-SS34")
      (libsource (lib "eagle-import") (part "SMA-SS34"))
    )
    (comp (ref "U$17")
      (value "SMA-SS34")
      (footprint "eagle-import:SMA-SS34")
      (libsource (lib "eagle-import") (part "SMA-SS34"))
    )
    (comp (ref "U$19")
      (value "18650SMD")
      (footprint "eagle-import:18650SMD")
      (libsource (lib "eagle-import") (part "18650SMD"))
    )
    (comp (ref "C1")
      (value "0.1uf")
      (footprint "eagle-import:C0603")
      (fields (field (name "MPN") "CC0603KRX5R6BB475"))
      (libsource (lib "eagle-import") (part "CERAMIC-4.7UF-10V-10%-X5R(0603)"))
    )
    (comp (ref "C2")
      (value "1uf")
      (footprint "eagle-import:C0603")
      (fields (field (name "MPN") "CC0603KRX5R6BB475"))
      (libsource (lib "eagle-import") (part "CERAMIC-4.7UF-10V-10%-X5R(0603)"))
    )
    (comp (ref "C3")
      (value "4.7uf")
      (footprint "eagle-import:C0603")
      (fields (field (name "MPN") "CC0603KRX5R6BB475"))
      (libsource (lib "eagle-import") (part "CERAMIC-4.7UF-10V-10%-X5R(0603)"))
    )
    (comp (ref "C36")
      (value "1uf")
      (footprint "eagle-import:C0603")
      (fields (field (name "MPN") "CC0603KRX5R6BB475"))
      (libsource (lib "eagle-import") (part "CERAMIC-4.7UF-10V-10%-X5R(0603)"))
    )
    (comp (ref "C37")
      (value "1uf")
      (footprint "eagle-import:C0603")
      (fields (field (name "MPN") "CC0603KRX5R6BB475"))
      (libsource (lib "eagle-import") (part "CERAMIC-4.7UF-10V-10%-X5R(0603)"))
    )
    (comp (ref "R38")
      (value "10k")
      (footprint "eagle-import:0603")
      (libsource (lib "eagle-import") (part "0OHM1/10W5%(0603)"))
    )
    (comp (ref "R39")
      (value "390k")
      (footprint "eagle-import:0603")
      (libsource (lib "eagle-import") (part "0OHM1/10W5%(0603)"))
    )
    (comp (ref "R40")
      (value "4.7k")
      (footprint "eagle-import:0603")
      (libsource (lib "eagle-import") (part "0OHM1/10W5%(0603)"))
    )
    (comp (ref "R41")
      (value "4.7k")
      (footprint "eagle-import:0603")
      (libsource (lib "eagle-import") (part "0OHM1/10W5%(0603)"))
    )
    (comp (ref "U$18")
      (value "ER-OLED0.96")
      (footprint "eagle-import:ER-OLED0.96")
      (libsource (lib "eagle-import") (part "ER-OLED0.96"))
    )
  )
  (nets
    (net (code "1") (name "+OUTPUT") (class "Default")
      (node (ref "R13") (pin "2") (pinfunction "2_2") (pintype "passive"))
      (node (ref "U$1") (pin "3") (pinfunction "3.+OUT_3") (pintype "bidirectional"))
    )
    (net (code "2") (name "-OUTPUT") (class "Default")
      (node (ref "R16") (pin "2") (pinfunction "2_2") (pintype "passive"))
      (node (ref "U$1") (pin "1") (pinfunction "1.-OUT_1") (pintype "bidirectional"))
      (node (ref "U$1") (pin "6") (pinfunction "6.-OUT_6") (pintype "bidirectional"))
    )
    (net (code "3") (name "AC") (class "Default")
      (node (ref "C35") (pin "2") (pinfunction "2_2") (pintype "passive"))
      (node (ref "R27") (pin "1") (pinfunction "1_1") (pintype "passive"))
      (node (ref "U$5") (pin "9") (pinfunction "PC1/ADC123_IN11(5T)_9") (pintype "bidirectional"))
      (node (ref "U2") (pin "8") (pinfunction "OUT2_8") (pintype "output"))
    )
    (net (code "4") (name "AGND") (class "Default")
      (node (ref "C30") (pin "1") (pinfunction "1_1") (pintype "passive"))
      (node (ref "C34") (pin "2") (pinfunction "2_2") (pintype "passive"))
      (node (ref "R2") (pin "2") (pinfunction "2_2") (pintype "passive"))
      (node (ref "R20") (pin "2") (pinfunction "2_2") (pintype "passive"))
      (node (ref "R22") (pin "2") (pinfunction "2_2") (pintype "passive"))
      (node (ref "R23") (pin "2") (pinfunction "2_2") (pintype "passive"))
      (node (ref "R28") (pin "2") (pinfunction "2_2") (pintype "passive"))
      (node (ref "R3") (pin "1") (pinfunction "1_1") (pintype "passive"))
      (node (ref "R34") (pin "2") (pinfunction "2_2") (pintype "passive"))
      (node (ref "R9") (pin "1") (pinfunction "1_1") (pintype "passive"))
      (node (ref "U$1") (pin "5") (pinfunction "5.-IN_5") (pintype "bidirectional"))
      (node (ref "U2") (pin "11") (pinfunction "GND_11") (pintype "power_in"))
      (node (ref "U3") (pin "4") (pinfunction "GND_4") (pintype "power_in"))
    )
    (net (code "5") (name "AIN1") (class "Default")
      (node (ref "IC1") (pin "21") (pinfunction "AIN1_21") (pintype "input"))
      (node (ref "U$5") (pin "58") (pinfunction "PB6/I2C1_SCL/USART1_TX/TIM4_CH1(5T)_58") (pintype "bidirectional"))
    )
    (net (code "6") (name "AIN2") (class "Default")
      (node (ref "IC1") (pin "22") (pinfunction "AIN2_22") (pintype "input"))
      (node (ref "U$5") (pin "59") (pinfunction "PB7/I2C1_SDA/USART1_RX/TIM4_CH2(5T)_59") (pintype "bidirectional"))
    )
    (net (code "7") (name "B1") (class "Default")
      (node (ref "C41") (pin "1") (pinfunction "1_1") (pintype "passive"))
      (node (ref "R8") (pin "1") (pinfunction "1_1") (pintype "passive"))
      (node (ref "S2") (pin "1") (pinfunction "1_1") (pintype "passive"))
      (node (ref "S2") (pin "2") (pinfunction "2_2") (pintype "passive"))
      (node (ref "U$5") (pin "14") (pinfunction "PA0/ADC123_IN0(5T)_14") (pintype "bidirectional"))
    )
    (net (code "8") (name "B2") (class "Default")
      (node (ref "C4") (pin "1") (pinfunction "1_1") (pintype "passive"))
      (node (ref "R1") (pin "1") (pinfunction "1_1") (pintype "passive"))
      (node (ref "S3") (pin "1") (pinfunction "1_1") (pintype "passive"))
      (node (ref "S3") (pin "2") (pinfunction "2_2") (pintype "passive"))
      (node (ref "U$5") (pin "15") (pinfunction "PA1/ADC123_IN1(5T)_15") (pintype "bidirectional"))
    )
    (net (code "9") (name "BAT") (class "Default")
      (node (ref "U$5") (pin "10") (pinfunction "PC2/ADC123_IN12(5T)_10") (pintype "bidirectional"))
      (node (ref "U2") (pin "13") (pinfunction "-IN2_13") (pintype "input"))
      (node (ref "U2") (pin "14") (pinfunction "OUT2_14") (pintype "output"))
    )
    (net (code "10") (name "BAT+") (class "Default")
      (node (ref "C29") (pin "+") (pinfunction "+_+") (pintype "passive"))
      (node (ref "C39") (pin "A") (pinfunction "+_A") (pintype "passive"))
      (node (ref "J1") (pin "1") (pinfunction "1_1") (pintype "passive"))
      (node (ref "R65") (pin "2") (pinfunction "2_2") (pintype "passive"))
      (node (ref "SW1") (pin "COM1") (pinfunction "COM1_COM1") (pintype "bidirectional"))
      (node (ref "U$4") (pin "B+") (pinfunction "B+_B+") (pintype "bidirectional"))
      (node (ref "U$6") (pin "5") (pinfunction "BAT_5") (pintype "bidirectional"))
    )
    (net (code "11") (name "BAT-") (class "Default")
      (node (ref "C29") (pin "-") (pinfunction "-_-") (pintype "passive"))
      (node (ref "C40") (pin "2") (pinfunction "2_2") (pintype "passive"))
      (node (ref "J2") (pin "1") (pinfunction "1_1") (pintype "passive"))
      (node (ref "T1") (pin "2") (pinfunction "S_2") (pintype "passive"))
      (node (ref "T1") (pin "3") (pinfunction "S_3") (pintype "passive"))
      (node (ref "U$4") (pin "B-") (pinfunction "B-_B-") (pintype "bidirectional"))
      (node (ref "U$7") (pin "6") (pinfunction "GND_6") (pintype "bidirectional"))
    )
    (net (code "12") (name "BIN1") (class "Default")
      (node (ref "IC1") (pin "17") (pinfunction "BIN1_17") (pintype "input"))
      (node (ref "U$5") (pin "62") (pinfunction "PB9/TIM11_CH1/TIM4_CH4(5T)_62") (pintype "bidirectional"))
    )
    (net (code "13") (name "BIN2") (class "Default")
      (node (ref "IC1") (pin "16") (pinfunction "BIN2_16") (pintype "input"))
      (node (ref "U$5") (pin "29") (pinfunction "PB10/I2C2_SCL(5T)_29") (pintype "bidirectional"))
    )
    (net (code "14") (name "BOOT0") (class "Default")
      (node (ref "R5") (pin "2") (pinfunction "2_2") (pintype "passive"))
      (node (ref "R6") (pin "2") (pinfunction "2_2") (pintype "passive"))
      (node (ref "U$5") (pin "60") (pinfunction "BOOT0_60") (pintype "bidirectional"))
    )
    (net (code "15") (name "BOOT1") (class "Default")
      (node (ref "R44") (pin "2") (pinfunction "2_2") (pintype "passive"))
      (node (ref "R45") (pin "2") (pinfunction "2_2") (pintype "passive"))
      (node (ref "U$5") (pin "28") (pinfunction "PB2/BOOT1(5T)_28") (pintype "bidirectional"))
    )
    (net (code "16") (name "DC") (class "Default")
      (node (ref "C31") (pin "1") (pinfunction "1_1") (pintype "passive"))
      (node (ref "R19") (pin "1") (pinfunction "1_1") (pintype "passive"))
      (node (ref "U$5") (pin "8") (pinfunction "PC0/ADC123_IN10(5T)_8") (pintype "bidirectional"))
      (node (ref "U2") (pin "1") (pinfunction "OUT1_1") (pintype "output"))
    )
    (net (code "17") (name "EXT_BAT") (class "Default")
      (node (ref "J1") (pin "3") (pinfunction "3_3") (pintype "passive"))
      (node (ref "JP1") (pin "3") (pinfunction "3_3") (pintype "passive"))
    )
    (net (code "18") (name "GND") (class "Default")
      (node (ref "C1") (pin "1") (pinfunction "1_1") (pintype "passive"))
      (node (ref "C10") (pin "1") (pinfunction "1_1") (pintype "passive"))
      (node (ref "C11") (pin "1") (pinfunction "1_1") (pintype "passive"))
      (node (ref "C12") (pin "1") (pinfunction "1_1") (pintype "passive"))
      (node (ref "C13") (pin "1") (pinfunction "1_1") (pintype "passive"))
      (node (ref "C14") (pin "1") (pinfunction "1_1") (pintype "passive"))
      (node (ref "C15") (pin "1") (pinfunction "1_1") (pintype "passive"))
      (node (ref "C16") (pin "2") (pinfunction "2_2") (pintype "passive"))
      (node (ref "C17") (pin "2") (pinfunction "2_2") (pintype "passive"))
      (node (ref "C18") (pin "1") (pinfunction "1_1") (pintype "passive"))
      (node (ref "C19") (pin "1") (pinfunction "1_1") (pintype "passive"))
      (node (ref "C20") (pin "1") (pinfunction "1_1") (pintype "passive"))
      (node (ref "C21") (pin "1") (pinfunction "1_1") (pintype "passive"))
      (node (ref "C22") (pin "2") (pinfunction "2_2") (pintype "passive"))
      (node (ref "C3") (pin "1") (pinfunction "1_1") (pintype "passive"))
      (node (ref "C37") (pin "1") (pinfunction "1_1") (pintype "passive"))
      (node (ref "C38") (pin "C") (pinfunction "-_C") (pintype "passive"))
      (node (ref "C39") (pin "C") (pinfunction "-_C") (pintype "passive"))
      (node (ref "C4") (pin "2") (pinfunction "2_2") (pintype "passive"))
      (node (ref "C41") (pin "2") (pinfunction "2_2") (pintype "passive"))
      (node (ref "C5") (pin "1") (pinfunction "1_1") (pintype "passive"))
      (node (ref "C6") (pin "1") (pinfunction "1_1") (pintype "passive"))
      (node (ref "C7") (pin "1") (pinfunction "1_1") (pintype "passive"))
      (node (ref "C8") (pin "1") (pinfunction "1_1") (pintype "passive"))
      (node (ref "C9") (pin "1") (pinfunction "1_1") (pintype "passive"))
      (node (ref "D2") (pin "C") (pinfunction "C_C") (pintype "passive"))
      (node (ref "D3") (pin "C") (pinfunction "C_C") (pintype "passive"))
      (node (ref "IC1") (pin "10") (pinfunction "PGND2'_10") (pintype "power_in"))
      (node (ref "IC1") (pin "18") (pinfunction "GND_18") (pintype "power_in"))
      (node (ref "IC1") (pin "3") (pinfunction "PGND1_3") (pintype "power_in"))
      (node (ref "IC1") (pin "4") (pinfunction "PGND1'_4") (pintype "power_in"))
      (node (ref "IC1") (pin "9") (pinfunction "PGND2_9") (pintype "power_in"))
      (node (ref "IC2") (pin "2") (pinfunction "GND_2") (pintype "power_in"))
      (node (ref "J2") (pin "3") (pinfunction "3_3") (pintype "passive"))
      (node (ref "JP2") (pin "2") (pinfunction "2_2") (pintype "passive"))
      (node (ref "R3") (pin "2") (pinfunction "2_2") (pintype "passive"))
      (node (ref "R39") (pin "2") (pinfunction "2_2") (pintype "passive"))
      (node (ref "R44") (pin "1") (pinfunction "1_1") (pintype "passive"))
      (node (ref "R48") (pin "1") (pinfunction "1_1") (pintype "passive"))
      (node (ref "R5") (pin "1") (pinfunction "1_1") (pintype "passive"))
      (node (ref "R62") (pin "1") (pinfunction "1_1") (pintype "passive"))
      (node (ref "R66") (pin "1") (pinfunction "1_1") (pintype "passive"))
      (node (ref "R9") (pin "2") (pinfunction "2_2") (pintype "passive"))
      (node (ref "S1") (pin "3") (pinfunction "3_3") (pintype "passive"))
      (node (ref "S1") (pin "4") (pinfunction "4_4") (pintype "passive"))
      (node (ref "S2") (pin "3") (pinfunction "3_3") (pintype "passive"))
      (node (ref "S2") (pin "4") (pinfunction "4_4") (pintype "passive"))
      (node (ref "S3") (pin "3") (pinfunction "3_3") (pintype "passive"))
      (node (ref "S3") (pin "4") (pinfunction "4_4") (pintype "passive"))
      (node (ref "T1") (pin "6") (pinfunction "S_6") (pintype "passive"))
      (node (ref "T1") (pin "7") (pinfunction "S_7") (pintype "passive"))
      (node (ref "U$14") (pin "1") (pinfunction "IN_1") (pintype "input"))
      (node (ref "U$17") (pin "1") (pinfunction "IN_1") (pintype "input"))
      (node (ref "U$18") (pin "P$10") (pinfunction "10.BS0_P$10") (pintype "bidirectional"))
      (node (ref "U$18") (pin "P$12") (pinfunction "12.BS2_P$12") (pintype "bidirectional"))
      (node (ref "U$18") (pin "P$13") (pinfunction "13.CS#_P$13") (pintype "bidirectional"))
      (node (ref "U$18") (pin "P$15") (pinfunction "15.D/C#_P$15") (pintype "bidirectional"))
      (node (ref "U$18") (pin "P$16") (pinfunction "16.R/W#_P$16") (pintype "bidirectional"))
      (node (ref "U$18") (pin "P$17") (pinfunction "17.E/RD#_P$17") (pintype "bidirectional"))
      (node (ref "U$18") (pin "P$21") (pinfunction "21.D3_P$21") (pintype "bidirectional"))
      (node (ref "U$18") (pin "P$22") (pinfunction "22.D4_P$22") (pintype "bidirectional"))
      (node (ref "U$18") (pin "P$23") (pinfunction "23.D5_P$23") (pintype "bidirectional"))
      (node (ref "U$18") (pin "P$24") (pinfunction "24.D6_P$24") (pintype "bidirectional"))
      (node (ref "U$18") (pin "P$25") (pinfunction "25.D7_P$25") (pintype "bidirectional"))
      (node (ref "U$18") (pin "P$29") (pinfunction "29.VLSS_P$29") (pintype "bidirectional"))
      (node (ref "U$18") (pin "P$8") (pinfunction "8.VSS_P$8") (pintype "bidirectional"))
      (node (ref "U$5") (pin "12") (pinfunction "VSSA_12") (pintype "bidirectional"))
      (node (ref "U$5") (pin "18") (pinfunction "VSS_1_18") (pintype "bidirectional"))
      (node (ref "U$5") (pin "63") (pinfunction "VSS_2_63") (pintype "bidirectional"))
      (node (ref "U$6") (pin "1") (pinfunction "TEMP_1") (pintype "bidirectional"))
      (node (ref "U$6") (pin "3") (pinfunction "GND_3") (pintype "bidirectional"))
      (node (ref "U1") (pin "GND") (pinfunction "GND_GND") (pintype "bidirectional"))
      (node (ref "U1") (pin "GND1") (pinfunction "GND_GND1") (pintype "bidirectional"))
    )
    (net (code "19") (name "I2C3_SCL") (class "Default")
      (node (ref "R41") (pin "2") (pinfunction "2_2") (pintype "passive"))
      (node (ref "U$18") (pin "P$18") (pinfunction "18.D0_P$18") (pintype "bidirectional"))
      (node (ref "U$5") (pin "41") (pinfunction "PA8/TIM1_CH1(5T)_41") (pintype "bidirectional"))
    )
    (net (code "20") (name "I2C3_SDA") (class "Default")
      (node (ref "R40") (pin "1") (pinfunction "1_1") (pintype "passive"))
      (node (ref "U$18") (pin "P$19") (pinfunction "19.D1_P$19") (pintype "bidirectional"))
      (node (ref "U$18") (pin "P$20") (pinfunction "20.D2_P$20") (pintype "bidirectional"))
      (node (ref "U$5") (pin "40") (pinfunction "PC9/TIM3_CH4/TIM8_CH4(5T)_40") (pintype "bidirectional"))
    )
    (net (code "21") (name "L+") (class "Default")
      (node (ref "C24") (pin "2") (pinfunction "2_2") (pintype "passive"))
      (node (ref "IC1") (pin "7") (pinfunction "BO2_7") (pintype "output"))
      (node (ref "IC1") (pin "8") (pinfunction "BO2'_8") (pintype "output"))
      (node (ref "U$11") (pin "1") (pinfunction "+_1") (pintype "bidirectional"))
    )
    (net (code "22") (name "L-") (class "Default")
      (node (ref "C24") (pin "1") (pinfunction "1_1") (pintype "passive"))
      (node (ref "IC1") (pin "11") (pinfunction "BO1_11") (pintype "output"))
      (node (ref "IC1") (pin "12") (pinfunction "BO1'_12") (pintype "output"))
      (node (ref "U$11") (pin "2") (pinfunction "-_2") (pintype "bidirectional"))
    )
    (net (code "23") (name "LED1") (class "Default")
      (node (ref "R46") (pin "2") (pinfunction "2_2") (pintype "passive"))
      (node (ref "U$5") (pin "53") (pinfunction "PC12(5T)_53") (pintype "bidirectional"))
    )
    (net (code "24") (name "LED2") (class "Default")
      (node (ref "R4") (pin "2") (pinfunction "2_2") (pintype "passive"))
      (node (ref "U$5") (pin "2") (pinfunction "PC13(5T)_2") (pintype "bidirectional"))
    )
    (net (code "25") (name "M+") (class "Default")
      (node (ref "C23") (pin "2") (pinfunction "2_2") (pintype "passive"))
      (node (ref "IC1") (pin "1") (pinfunction "AO1_1") (pintype "output"))
      (node (ref "IC1") (pin "2") (pinfunction "AO1'_2") (pintype "output"))
      (node (ref "U$12") (pin "1") (pinfunction "+_1") (pintype "bidirectional"))
      (node (ref "U$13") (pin "1") (pinfunction "IN_1") (pintype "input"))
      (node (ref "U$14") (pin "2") (pinfunction "OUT_2") (pintype "bidirectional"))
    )
    (net (code "26") (name "M-") (class "Default")
      (node (ref "C23") (pin "1") (pinfunction "1_1") (pintype "passive"))
      (node (ref "IC1") (pin "5") (pinfunction "AO2_5") (pintype "output"))
      (node (ref "IC1") (pin "6") (pinfunction "AO2'_6") (pintype "output"))
      (node (ref "U$12") (pin "2") (pinfunction "-_2") (pintype "bidirectional"))
      (node (ref "U$16") (pin "1") (pinfunction "IN_1") (pintype "input"))
      (node (ref "U$17") (pin "2") (pinfunction "OUT_2") (pintype "bidirectional"))
    )
    (net (code "27") (name "MCU_3V3") (class "Default")
      (node (ref "C10") (pin "2") (pinfunction "2_2") (pintype "passive"))
      (node (ref "C11") (pin "2") (pinfunction "2_2") (pintype "passive"))
      (node (ref "C8") (pin "2") (pinfunction "2_2") (pintype "passive"))
      (node (ref "C9") (pin "2") (pinfunction "2_2") (pintype "passive"))
      (node (ref "D1") (pin "1") (pinfunction "C_1") (pintype "passive"))
      (node (ref "IC1") (pin "20") (pinfunction "VCC_20") (pintype "power_in"))
      (node (ref "R1") (pin "2") (pinfunction "2_2") (pintype "passive"))
      (node (ref "R30") (pin "1") (pinfunction "1_1") (pintype "passive"))
      (node (ref "R35") (pin "1") (pinfunction "1_1") (pintype "passive"))
      (node (ref "R36") (pin "2") (pinfunction "2_2") (pintype "passive"))
      (node (ref "R37") (pin "2") (pinfunction "2_2") (pintype "passive"))
      (node (ref "R40") (pin "2") (pinfunction "2_2") (pintype "passive"))
      (node (ref "R41") (pin "1") (pinfunction "1_1") (pintype "passive"))
      (node (ref "R45") (pin "1") (pinfunction "1_1") (pintype "passive"))
      (node (ref "R6") (pin "1") (pinfunction "1_1") (pintype "passive"))
      (node (ref "R7") (pin "2") (pinfunction "2_2") (pintype "passive"))
      (node (ref "R8") (pin "2") (pinfunction "2_2") (pintype "passive"))
      (node (ref "U$10") (pin "1") (pinfunction "1.IN_1") (pintype "bidirectional"))
      (node (ref "U$5") (pin "1") (pinfunction "VBAT_1") (pintype "bidirectional"))
      (node (ref "U$5") (pin "19") (pinfunction "VDD_1_19") (pintype "bidirectional"))
      (node (ref "U$5") (pin "32") (pinfunction "VDD_2_32") (pintype "bidirectional"))
      (node (ref "U$5") (pin "48") (pinfunction "VDD_3_48") (pintype "bidirectional"))
      (node (ref "U$5") (pin "64") (pinfunction "VDD_4_64") (pintype "bidirectional"))
      (node (ref "U2") (pin "4") (pinfunction "+V_4") (pintype "power_in"))
      (node (ref "U3") (pin "8") (pinfunction "+V_8") (pintype "power_in"))
      (node (ref "U4") (pin "2") (pinfunction "E_2") (pintype "passive"))
    )
    (net (code "28") (name "NRST") (class "Default")
      (node (ref "C22") (pin "1") (pinfunction "1_1") (pintype "passive"))
      (node (ref "R7") (pin "1") (pinfunction "1_1") (pintype "passive"))
      (node (ref "S1") (pin "1") (pinfunction "1_1") (pintype "passive"))
      (node (ref "S1") (pin "2") (pinfunction "2_2") (pintype "passive"))
      (node (ref "U$5") (pin "7") (pinfunction "NRST_7") (pintype "bidirectional"))
    )
    (net (code "29") (name "Net-(C31-Pad2)") (class "Default")
      (node (ref "C31") (pin "2") (pinfunction "2_2") (pintype "passive"))
      (node (ref "R17") (pin "1") (pinfunction "1_1") (pintype "passive"))
      (node (ref "R18") (pin "2") (pinfunction "2_2") (pintype "passive"))
    )
    (net (code "30") (name "Net-(C32-Pad2)") (class "Default")
      (node (ref "C32") (pin "2") (pinfunction "2_2") (pintype "passive"))
      (node (ref "C33") (pin "1") (pinfunction "1_1") (pintype "passive"))
      (node (ref "R21") (pin "2") (pinfunction "2_2") (pintype "passive"))
    )
    (net (code "31") (name "Net-(D1-A)") (class "Default")
      (node (ref "C7") (pin "2") (pinfunction "2_2") (pintype "passive"))
      (node (ref "D1") (pin "2") (pinfunction "A_2") (pintype "passive"))
      (node (ref "IC2") (pin "5") (pinfunction "VO_5") (pintype "output"))
    )
    (net (code "32") (name "Net-(D2-PadA)") (class "Default")
      (node (ref "D2") (pin "A") (pinfunction "A_A") (pintype "passive"))
      (node (ref "R4") (pin "1") (pinfunction "1_1") (pintype "passive"))
    )
    (net (code "33") (name "Net-(D3-PadA)") (class "Default")
      (node (ref "D3") (pin "A") (pinfunction "A_A") (pintype "passive"))
      (node (ref "R46") (pin "1") (pinfunction "1_1") (pintype "passive"))
    )
    (net (code "34") (name "Net-(D5-PadC)") (class "Default")
      (node (ref "D5") (pin "C") (pinfunction "C_C") (pintype "passive"))
      (node (ref "R64") (pin "2") (pinfunction "2_2") (pintype "passive"))
    )
    (net (code "35") (name "Net-(D6-PadC)") (class "Default")
      (node (ref "D6") (pin "C") (pinfunction "C_C") (pintype "passive"))
      (node (ref "R63") (pin "2") (pinfunction "2_2") (pintype "passive"))
    )
    (net (code "36") (name "Net-(IC2-BYPASS)") (class "Default")
      (node (ref "C6") (pin "2") (pinfunction "2_2") (pintype "passive"))
      (node (ref "IC2") (pin "4") (pinfunction "BYPASS_4") (pintype "passive"))
    )
    (net (code "37") (name "Net-(J1-Pad2)") (class "Default")
      (node (ref "J1") (pin "2") (pinfunction "2_2") (pintype "passive"))
      (node (ref "U$19") (pin "B+") (pinfunction "B+_B+") (pintype "bidirectional"))
    )
    (net (code "38") (name "Net-(J2-Pad2)") (class "Default")
      (node (ref "J2") (pin "2") (pinfunction "2_2") (pintype "passive"))
      (node (ref "U$19") (pin "B-") (pinfunction "B-_B-") (pintype "bidirectional"))
    )
    (net (code "39") (name "Net-(R11-Pad1)") (class "Default")
      (node (ref "R11") (pin "1") (pinfunction "1_1") (pintype "passive"))
      (node (ref "R12") (pin "2") (pinfunction "2_2") (pintype "passive"))
    )
    (net (code "40") (name "Net-(R32-Pad2)") (class "Default")
      (node (ref "R32") (pin "2") (pinfunction "2_2") (pintype "passive"))
      (node (ref "R33") (pin "1") (pinfunction "1_1") (pintype "passive"))
    )
    (net (code "41") (name "Net-(R33-Pad2)") (class "Default")
      (node (ref "R33") (pin "2") (pinfunction "2_2") (pintype "passive"))
      (node (ref "R34") (pin "1") (pinfunction "1_1") (pintype "passive"))
      (node (ref "R35") (pin "2") (pinfunction "2_2") (pintype "passive"))
    )
    (net (code "42") (name "Net-(T1A-D)") (class "Default")
      (node (ref "T1") (pin "1") (pinfunction "D_1") (pintype "passive"))
      (node (ref "T1") (pin "8") (pinfunction "D_8") (pintype "passive"))
    )
    (net (code "43") (name "Net-(T1A-G)") (class "Default")
      (node (ref "T1") (pin "4") (pinfunction "G_4") (pintype "passive"))
      (node (ref "U$7") (pin "1") (pinfunction "0D_1") (pintype "bidirectional"))
    )
    (net (code "44") (name "Net-(T1B-G)") (class "Default")
      (node (ref "T1") (pin "5") (pinfunction "G_5") (pintype "passive"))
      (node (ref "U$7") (pin "3") (pinfunction "0C_3") (pintype "bidirectional"))
    )
    (net (code "45") (name "Net-(U$1-2.+IN)") (class "Default")
      (node (ref "R29") (pin "2") (pinfunction "2_2") (pintype "passive"))
      (node (ref "R37") (pin "1") (pinfunction "1_1") (pintype "passive"))
      (node (ref "U$1") (pin "2") (pinfunction "2.+IN_2") (pintype "bidirectional"))
    )
    (net (code "46") (name "Net-(U$5-VCAP_1)") (class "Default")
      (node (ref "C17") (pin "1") (pinfunction "1_1") (pintype "passive"))
      (node (ref "U$5") (pin "31") (pinfunction "VCAP_1_31") (pintype "bidirectional"))
    )
    (net (code "47") (name "Net-(U$5-VCAP_2)") (class "Default")
      (node (ref "C16") (pin "1") (pinfunction "1_1") (pintype "passive"))
      (node (ref "U$5") (pin "47") (pinfunction "VCAP_2_47") (pintype "bidirectional"))
    )
    (net (code "48") (name "Net-(U$6-PROG)") (class "Default")
      (node (ref "R62") (pin "2") (pinfunction "2_2") (pintype "passive"))
      (node (ref "U$6") (pin "2") (pinfunction "PROG_2") (pintype "bidirectional"))
    )
    (net (code "49") (name "Net-(U$6-~{CHRG})") (class "Default")
      (node (ref "R63") (pin "1") (pinfunction "1_1") (pintype "passive"))
      (node (ref "U$6") (pin "7") (pinfunction "~{CHRG}_7") (pintype "bidirectional"))
    )
    (net (code "50") (name "Net-(U$6-~{STDBY})") (class "Default")
      (node (ref "R64") (pin "1") (pinfunction "1_1") (pintype "passive"))
      (node (ref "U$6") (pin "6") (pinfunction "~{STDBY}_6") (pintype "bidirectional"))
    )
    (net (code "51") (name "Net-(U$7-CS)") (class "Default")
      (node (ref "R66") (pin "2") (pinfunction "2_2") (pintype "passive"))
      (node (ref "U$7") (pin "2") (pinfunction "CS_2") (pintype "bidirectional"))
    )
    (net (code "52") (name "Net-(U$7-VCC)") (class "Default")
      (node (ref "C40") (pin "1") (pinfunction "1_1") (pintype "passive"))
      (node (ref "R65") (pin "1") (pinfunction "1_1") (pintype "passive"))
      (node (ref "U$7") (pin "5") (pinfunction "VCC_5") (pintype "bidirectional"))
    )
    (net (code "53") (name "Net-(U$15-1.IN)") (class "Default")
      (node (ref "U$15") (pin "1") (pinfunction "1.IN_1") (pintype "bidirectional"))
      (node (ref "U1") (pin "VBUS1") (pinfunction "VBUS_VBUS1") (pintype "bidirectional"))
    )
    (net (code "54") (name "Net-(U$15-2.OUT)") (class "Default")
      (node (ref "R42") (pin "2") (pinfunction "2_2") (pintype "passive"))
      (node (ref "U$15") (pin "2") (pinfunction "2.OUT_2") (pintype "bidirectional"))
    )
    (net (code "55") (name "Net-(U$18-2.C2P)") (class "Default")
      (node (ref "C2") (pin "2") (pinfunction "2_2") (pintype "passive"))
      (node (ref "U$18") (pin "P$2") (pinfunction "2.C2P_P$2") (pintype "bidirectional"))
    )
    (net (code "56") (name "Net-(U$18-3.C2N)") (class "Default")
      (node (ref "C2") (pin "1") (pinfunction "1_1") (pintype "passive"))
      (node (ref "U$18") (pin "P$3") (pinfunction "3.C2N_P$3") (pintype "bidirectional"))
    )
    (net (code "57") (name "Net-(U$18-4.C1P)") (class "Default")
      (node (ref "C36") (pin "2") (pinfunction "2_2") (pintype "passive"))
      (node (ref "U$18") (pin "P$4") (pinfunction "4.C1P_P$4") (pintype "bidirectional"))
    )
    (net (code "58") (name "Net-(U$18-5.C1N)") (class "Default")
      (node (ref "C36") (pin "1") (pinfunction "1_1") (pintype "passive"))
      (node (ref "U$18") (pin "P$5") (pinfunction "5.C1N_P$5") (pintype "bidirectional"))
    )
    (net (code "59") (name "Net-(U$18-14.RES#)") (class "Default")
      (node (ref "C1") (pin "2") (pinfunction "2_2") (pintype "passive"))
      (node (ref "R38") (pin "2") (pinfunction "2_2") (pintype "passive"))
      (node (ref "U$18") (pin "P$14") (pinfunction "14.RES#_P$14") (pintype "bidirectional"))
    )
    (net (code "60") (name "Net-(U$18-26.IREF)") (class "Default")
      (node (ref "R39") (pin "1") (pinfunction "1_1") (pintype "passive"))
      (node (ref "U$18") (pin "P$26") (pinfunction "26.IREF_P$26") (pintype "bidirectional"))
    )
    (net (code "61") (name "Net-(U$18-27.VCOMH)") (class "Default")
      (node (ref "C3") (pin "2") (pinfunction "2_2") (pintype "passive"))
      (node (ref "U$18") (pin "P$27") (pinfunction "27.VCOMH_P$27") (pintype "bidirectional"))
    )
    (net (code "62") (name "Net-(U$18-28.VCC)") (class "Default")
      (node (ref "C37") (pin "2") (pinfunction "2_2") (pintype "passive"))
      (node (ref "U$18") (pin "P$28") (pinfunction "28.VCC_P$28") (pintype "bidirectional"))
    )
    (net (code "63") (name "Net-(U1-D+)") (class "Default")
      (node (ref "R15") (pin "2") (pinfunction "2_2") (pintype "passive"))
      (node (ref "U1") (pin "D+1") (pinfunction "D+_D+1") (pintype "bidirectional"))
    )
    (net (code "64") (name "Net-(U1-D-)") (class "Default")
      (node (ref "R14") (pin "2") (pinfunction "2_2") (pintype "passive"))
      (node (ref "U1") (pin "D-1") (pinfunction "D-_D-1") (pintype "bidirectional"))
    )
    (net (code "65") (name "Net-(U1-USBID)") (class "Default")
      (node (ref "R43") (pin "2") (pinfunction "2_2") (pintype "passive"))
      (node (ref "U1") (pin "ID1") (pinfunction "USBID_ID1") (pintype "bidirectional"))
    )
    (net (code "66") (name "Net-(U2A-+IN1)") (class "Default")
      (node (ref "C30") (pin "2") (pinfunction "2_2") (pintype "passive"))
      (node (ref "R18") (pin "1") (pinfunction "1_1") (pintype "passive"))
      (node (ref "U2") (pin "3") (pinfunction "+IN1_3") (pintype "input"))
    )
    (net (code "67") (name "Net-(U2A--IN1)") (class "Default")
      (node (ref "R19") (pin "2") (pinfunction "2_2") (pintype "passive"))
      (node (ref "R20") (pin "1") (pinfunction "1_1") (pintype "passive"))
      (node (ref "U2") (pin "2") (pinfunction "-IN1_2") (pintype "input"))
    )
    (net (code "68") (name "Net-(U2B-+IN2)") (class "Default")
      (node (ref "C32") (pin "1") (pinfunction "1_1") (pintype "passive"))
      (node (ref "R22") (pin "1") (pinfunction "1_1") (pintype "passive"))
      (node (ref "U2") (pin "5") (pinfunction "+IN2_5") (pintype "input"))
    )
    (net (code "69") (name "Net-(U2B--IN2)") (class "Default")
      (node (ref "R23") (pin "1") (pinfunction "1_1") (pintype "passive"))
      (node (ref "R24") (pin "2") (pinfunction "2_2") (pintype "passive"))
      (node (ref "U2") (pin "6") (pinfunction "-IN2_6") (pintype "input"))
    )
    (net (code "70") (name "Net-(U2B-OUT2)") (class "Default")
      (node (ref "R21") (pin "1") (pinfunction "1_1") (pintype "passive"))
      (node (ref "R24") (pin "1") (pinfunction "1_1") (pintype "passive"))
      (node (ref "R25") (pin "1") (pinfunction "1_1") (pintype "passive"))
      (node (ref "U2") (pin "7") (pinfunction "OUT2_7") (pintype "output"))
    )
    (net (code "71") (name "Net-(U2C-+IN2)") (class "Default")
      (node (ref "C34") (pin "1") (pinfunction "1_1") (pintype "passive"))
      (node (ref "R26") (pin "2") (pinfunction "2_2") (pintype "passive"))
      (node (ref "U2") (pin "10") (pinfunction "+IN2_10") (pintype "input"))
    )
    (net (code "72") (name "Net-(U2C--IN2)") (class "Default")
      (node (ref "R27") (pin "2") (pinfunction "2_2") (pintype "passive"))
      (node (ref "R28") (pin "1") (pinfunction "1_1") (pintype "passive"))
      (node (ref "U2") (pin "9") (pinfunction "-IN2_9") (pintype "input"))
    )
    (net (code "73") (name "Net-(U2D-+IN2)") (class "Default")
      (node (ref "R47") (pin "1") (pinfunction "1_1") (pintype "passive"))
      (node (ref "R48") (pin "2") (pinfunction "2_2") (pintype "passive"))
      (node (ref "U2") (pin "12") (pinfunction "+IN2_12") (pintype "input"))
    )
    (net (code "74") (name "Net-(U3A-+IN1)") (class "Default")
      (node (ref "R13") (pin "1") (pinfunction "1_1") (pintype "passive"))
      (node (ref "R32") (pin "1") (pinfunction "1_1") (pintype "passive"))
      (node (ref "U3") (pin "3") (pinfunction "+IN1_3") (pintype "input"))
    )
    (net (code "75") (name "Net-(U3A--IN1)") (class "Default")
      (node (ref "R11") (pin "2") (pinfunction "2_2") (pintype "passive"))
      (node (ref "R16") (pin "1") (pinfunction "1_1") (pintype "passive"))
      (node (ref "U3") (pin "2") (pinfunction "-IN1_2") (pintype "input"))
    )
    (net (code "76") (name "Net-(U3A-OUT1)") (class "Default")
      (node (ref "C33") (pin "2") (pinfunction "2_2") (pintype "passive"))
      (node (ref "R12") (pin "1") (pinfunction "1_1") (pintype "passive"))
      (node (ref "R17") (pin "2") (pinfunction "2_2") (pintype "passive"))
      (node (ref "U3") (pin "1") (pinfunction "OUT1_1") (pintype "output"))
    )
    (net (code "77") (name "Net-(U3B-+IN2)") (class "Default")
      (node (ref "R25") (pin "2") (pinfunction "2_2") (pintype "passive"))
      (node (ref "U3") (pin "5") (pinfunction "+IN2_5") (pintype "input"))
    )
    (net (code "78") (name "Net-(U3B--IN2)") (class "Default")
      (node (ref "R10") (pin "1") (pinfunction "1_1") (pintype "passive"))
      (node (ref "R2") (pin "1") (pinfunction "1_1") (pintype "passive"))
      (node (ref "U3") (pin "6") (pinfunction "-IN2_6") (pintype "input"))
    )
    (net (code "79") (name "Net-(U3B-OUT2)") (class "Default")
      (node (ref "C35") (pin "1") (pinfunction "1_1") (pintype "passive"))
      (node (ref "R10") (pin "2") (pinfunction "2_2") (pintype "passive"))
      (node (ref "R26") (pin "1") (pinfunction "1_1") (pintype "passive"))
      (node (ref "U3") (pin "7") (pinfunction "OUT2_7") (pintype "output"))
    )
    (net (code "80") (name "Net-(U4-B)") (class "Default")
      (node (ref "R30") (pin "2") (pinfunction "2_2") (pintype "passive"))
      (node (ref "R31") (pin "1") (pinfunction "1_1") (pintype "passive"))
      (node (ref "R36") (pin "1") (pinfunction "1_1") (pintype "passive"))
      (node (ref "U4") (pin "1") (pinfunction "B_1") (pintype "passive"))
    )
    (net (code "81") (name "Net-(U4-C)") (class "Default")
      (node (ref "R29") (pin "1") (pinfunction "1_1") (pintype "passive"))
      (node (ref "U4") (pin "3") (pinfunction "C_3") (pintype "passive"))
    )
    (net (code "82") (name "OSC32_IN") (class "Default")
      (node (ref "C21") (pin "2") (pinfunction "2_2") (pintype "passive"))
      (node (ref "U$5") (pin "3") (pinfunction "PC14/OSC32_IN(5T)_3") (pintype "bidirectional"))
      (node (ref "U$8") (pin "1") (pinfunction "1.XIN_1") (pintype "bidirectional"))
    )
    (net (code "83") (name "OSC32_OUT") (class "Default")
      (node (ref "C20") (pin "2") (pinfunction "2_2") (pintype "passive"))
      (node (ref "U$5") (pin "4") (pinfunction "PC15/OSC32_OUT(5T)_4") (pintype "bidirectional"))
      (node (ref "U$8") (pin "2") (pinfunction "2.XIN_2") (pintype "bidirectional"))
    )
    (net (code "84") (name "OSC_IN") (class "Default")
      (node (ref "C19") (pin "2") (pinfunction "2_2") (pintype "passive"))
      (node (ref "U$5") (pin "5") (pinfunction "PH0/OSC_IN(5T)_5") (pintype "bidirectional"))
      (node (ref "U$9") (pin "1") (pinfunction "1.XIN_1") (pintype "bidirectional"))
    )
    (net (code "85") (name "OSC_OUT") (class "Default")
      (node (ref "C18") (pin "2") (pinfunction "2_2") (pintype "passive"))
      (node (ref "U$5") (pin "6") (pinfunction "PH1/OSC_OUT(5T)_6") (pintype "bidirectional"))
      (node (ref "U$9") (pin "2") (pinfunction "2.XOUT_2") (pintype "bidirectional"))
    )
    (net (code "86") (name "OTG_FS_DM") (class "Default")
      (node (ref "R14") (pin "1") (pinfunction "1_1") (pintype "passive"))
      (node (ref "U$5") (pin "44") (pinfunction "PA11/TIM1_CH4/CANRX/USBDM(5T)_44") (pintype "bidirectional"))
    )
    (net (code "87") (name "OTG_FS_DP") (class "Default")
      (node (ref "R15") (pin "1") (pinfunction "1_1") (pintype "passive"))
      (node (ref "U$5") (pin "45") (pinfunction "PA12/CANTX/USBDP(5T)_45") (pintype "bidirectional"))
    )
    (net (code "88") (name "OTG_FS_ID") (class "Default")
      (node (ref "R43") (pin "1") (pinfunction "1_1") (pintype "passive"))
      (node (ref "U$5") (pin "43") (pinfunction "PA10/TIM1_CH3/USART1_RX(5T)_43") (pintype "bidirectional"))
    )
    (net (code "89") (name "PWM") (class "Default")
      (node (ref "R31") (pin "2") (pinfunction "2_2") (pintype "passive"))
      (node (ref "U$5") (pin "39") (pinfunction "PC8/TIM3_CH3/TIM8_CH3(5T)_39") (pintype "bidirectional"))
    )
    (net (code "90") (name "PWMA") (class "Default")
      (node (ref "IC1") (pin "23") (pinfunction "PWMA_23") (pintype "input"))
      (node (ref "U$5") (pin "57") (pinfunction "PB5(5T)_57") (pintype "bidirectional"))
    )
    (net (code "91") (name "PWMB") (class "Default")
      (node (ref "IC1") (pin "15") (pinfunction "PWMB_15") (pintype "input"))
      (node (ref "U$5") (pin "61") (pinfunction "PB8/TIM10_CH1/TIM4_CH3(5T)_61") (pintype "bidirectional"))
    )
    (net (code "92") (name "STBY") (class "Default")
      (node (ref "IC1") (pin "19") (pinfunction "STBY_19") (pintype "input"))
      (node (ref "U$5") (pin "30") (pinfunction "PB11/I2C2_SDA(5T)_30") (pintype "bidirectional"))
    )
    (net (code "93") (name "SWTCK") (class "Default")
      (node (ref "JP2") (pin "3") (pinfunction "3_3") (pintype "passive"))
      (node (ref "U$5") (pin "49") (pinfunction "PA14/JTCK-SWCLK(5T)_49") (pintype "bidirectional"))
    )
    (net (code "94") (name "SWTDIO") (class "Default")
      (node (ref "JP2") (pin "4") (pinfunction "4_4") (pintype "passive"))
      (node (ref "U$5") (pin "46") (pinfunction "PA13/JTMS-SWDAT(5T)_46") (pintype "bidirectional"))
    )
    (net (code "95") (name "VBUS") (class "Default")
      (node (ref "C38") (pin "A") (pinfunction "+_A") (pintype "passive"))
      (node (ref "D5") (pin "A") (pinfunction "A_A") (pintype "passive"))
      (node (ref "D6") (pin "A") (pinfunction "A_A") (pintype "passive"))
      (node (ref "R42") (pin "1") (pinfunction "1_1") (pintype "passive"))
      (node (ref "U$5") (pin "42") (pinfunction "PA9/TIM1_CH2/USART1_TX(5T)_42") (pintype "bidirectional"))
      (node (ref "U$6") (pin "4") (pinfunction "VCC_4") (pintype "bidirectional"))
      (node (ref "U$6") (pin "8") (pinfunction "CE_8") (pintype "bidirectional"))
    )
    (net (code "96") (name "VCC") (class "Default")
      (node (ref "C5") (pin "2") (pinfunction "2_2") (pintype "passive"))
      (node (ref "IC2") (pin "1") (pinfunction "VIN_1") (pintype "input"))
      (node (ref "IC2") (pin "3") (pinfunction "VINH_3") (pintype "input"))
      (node (ref "JP1") (pin "1") (pinfunction "1_1") (pintype "passive"))
      (node (ref "JP2") (pin "1") (pinfunction "1_1") (pintype "passive"))
      (node (ref "R38") (pin "1") (pinfunction "1_1") (pintype "passive"))
      (node (ref "R47") (pin "2") (pinfunction "2_2") (pintype "passive"))
      (node (ref "SW1") (pin "CH1A") (pinfunction "CH1A_CH1A") (pintype "bidirectional"))
      (node (ref "U$18") (pin "P$11") (pinfunction "11.BS1_P$11") (pintype "bidirectional"))
      (node (ref "U$18") (pin "P$6") (pinfunction "6.VBAT_P$6") (pintype "bidirectional"))
      (node (ref "U$18") (pin "P$9") (pinfunction "9.VDD_P$9") (pintype "bidirectional"))
    )
    (net (code "97") (name "VDDA") (class "Default")
      (node (ref "C12") (pin "2") (pinfunction "2_2") (pintype "passive"))
      (node (ref "C13") (pin "2") (pinfunction "2_2") (pintype "passive"))
      (node (ref "C14") (pin "2") (pinfunction "2_2") (pintype "passive"))
      (node (ref "C15") (pin "2") (pinfunction "2_2") (pintype "passive"))
      (node (ref "U$10") (pin "2") (pinfunction "2.OUT_2") (pintype "bidirectional"))
      (node (ref "U$5") (pin "13") (pinfunction "VDDA_13") (pintype "bidirectional"))
    )
    (net (code "98") (name "VM") (class "Default")
      (node (ref "IC1") (pin "13") (pinfunction "VM2_13") (pintype "power_in"))
      (node (ref "IC1") (pin "14") (pinfunction "VM3_14") (pintype "power_in"))
      (node (ref "IC1") (pin "24") (pinfunction "VM1_24") (pintype "power_in"))
      (node (ref "JP1") (pin "2") (pinfunction "2_2") (pintype "passive"))
      (node (ref "U$13") (pin "2") (pinfunction "OUT_2") (pintype "bidirectional"))
      (node (ref "U$16") (pin "2") (pinfunction "OUT_2") (pintype "bidirectional"))
    )
    (net (code "99") (name "unconnected-(SW1-PadCH1B)") (class "Default")
      (node (ref "SW1") (pin "CH1B") (pinfunction "CH1B_CH1B") (pintype "bidirectional"))
    )
    (net (code "100") (name "unconnected-(SW1-PadCH2A)") (class "Default")
      (node (ref "SW1") (pin "CH2A") (pinfunction "CH2A_CH2A") (pintype "bidirectional"))
    )
    (net (code "101") (name "unconnected-(SW1-PadCH2B)") (class "Default")
      (node (ref "SW1") (pin "CH2B") (pinfunction "CH2B_CH2B") (pintype "bidirectional"))
    )
    (net (code "102") (name "unconnected-(SW1-PadCOM2)") (class "Default")
      (node (ref "SW1") (pin "COM2") (pinfunction "COM2_COM2") (pintype "bidirectional"))
    )
    (net (code "103") (name "unconnected-(U$1-Pad4)") (class "Default")
      (node (ref "U$1") (pin "4") (pinfunction "4_4") (pintype "bidirectional"))
    )
    (net (code "104") (name "unconnected-(U$5-PA2{slash}ADC123_IN2(5T)-Pad16)") (class "Default")
      (node (ref "U$5") (pin "16") (pinfunction "PA2/ADC123_IN2(5T)_16") (pintype "bidirectional"))
    )
    (net (code "105") (name "unconnected-(U$5-PA3{slash}ADC123_IN3(5T)-Pad17)") (class "Default")
      (node (ref "U$5") (pin "17") (pinfunction "PA3/ADC123_IN3(5T)_17") (pintype "bidirectional"))
    )
    (net (code "106") (name "unconnected-(U$5-PA4{slash}ADC12_IN4-Pad20)") (class "Default")
      (node (ref "U$5") (pin "20") (pinfunction "PA4/ADC12_IN4_20") (pintype "bidirectional"))
    )
    (net (code "107") (name "unconnected-(U$5-PA5{slash}ADC12_IN5-Pad21)") (class "Default")
      (node (ref "U$5") (pin "21") (pinfunction "PA5/ADC12_IN5_21") (pintype "bidirectional"))
    )
    (net (code "108") (name "unconnected-(U$5-PA6{slash}ADC12_IN6(5T)-Pad22)") (class "Default")
      (node (ref "U$5") (pin "22") (pinfunction "PA6/ADC12_IN6(5T)_22") (pintype "bidirectional"))
    )
    (net (code "109") (name "unconnected-(U$5-PA7{slash}TIM1_CH1N{slash}ADC12_IN7(FT)-Pad23)") (class "Default")
      (node (ref "U$5") (pin "23") (pinfunction "PA7/TIM1_CH1N/ADC12_IN7(FT)_23") (pintype "bidirectional"))
    )
    (net (code "110") (name "unconnected-(U$5-PA15{slash}JTDI(5T)-Pad50)") (class "Default")
      (node (ref "U$5") (pin "50") (pinfunction "PA15/JTDI(5T)_50") (pintype "bidirectional"))
    )
    (net (code "111") (name "unconnected-(U$5-PB0{slash}TIM1_CH2N{slash}ADC12_IN8(5T)-Pad26)") (class "Default")
      (node (ref "U$5") (pin "26") (pinfunction "PB0/TIM1_CH2N/ADC12_IN8(5T)_26") (pintype "bidirectional"))
    )
    (net (code "112") (name "unconnected-(U$5-PB1{slash}TIM1_CH3N{slash}ADC12_IN9(5T)-Pad27)") (class "Default")
      (node (ref "U$5") (pin "27") (pinfunction "PB1/TIM1_CH3N/ADC12_IN9(5T)_27") (pintype "bidirectional"))
    )
    (net (code "113") (name "unconnected-(U$5-PB3{slash}JTDO(5T)-Pad55)") (class "Default")
      (node (ref "U$5") (pin "55") (pinfunction "PB3/JTDO(5T)_55") (pintype "bidirectional"))
    )
    (net (code "114") (name "unconnected-(U$5-PB4{slash}JNTRST(5T)-Pad56)") (class "Default")
      (node (ref "U$5") (pin "56") (pinfunction "PB4/JNTRST(5T)_56") (pintype "bidirectional"))
    )
    (net (code "115") (name "unconnected-(U$5-PB12(5T)-Pad33)") (class "Default")
      (node (ref "U$5") (pin "33") (pinfunction "PB12(5T)_33") (pintype "bidirectional"))
    )
    (net (code "116") (name "unconnected-(U$5-PB13{slash}SPI2_SCK(5T)-Pad34)") (class "Default")
      (node (ref "U$5") (pin "34") (pinfunction "PB13/SPI2_SCK(5T)_34") (pintype "bidirectional"))
    )
    (net (code "117") (name "unconnected-(U$5-PB14{slash}SPI2_MISO(5T)-Pad35)") (class "Default")
      (node (ref "U$5") (pin "35") (pinfunction "PB14/SPI2_MISO(5T)_35") (pintype "bidirectional"))
    )
    (net (code "118") (name "unconnected-(U$5-PB15{slash}SPI2_MOSI(5T)-Pad36)") (class "Default")
      (node (ref "U$5") (pin "36") (pinfunction "PB15/SPI2_MOSI(5T)_36") (pintype "bidirectional"))
    )
    (net (code "119") (name "unconnected-(U$5-PC3{slash}ADC123_IN13(5T)-Pad11)") (class "Default")
      (node (ref "U$5") (pin "11") (pinfunction "PC3/ADC123_IN13(5T)_11") (pintype "bidirectional"))
    )
    (net (code "120") (name "unconnected-(U$5-PC4{slash}ADC12_IN14-Pad24)") (class "Default")
      (node (ref "U$5") (pin "24") (pinfunction "PC4/ADC12_IN14_24") (pintype "bidirectional"))
    )
    (net (code "121") (name "unconnected-(U$5-PC5{slash}ADC12_IN15-Pad25)") (class "Default")
      (node (ref "U$5") (pin "25") (pinfunction "PC5/ADC12_IN15_25") (pintype "bidirectional"))
    )
    (net (code "122") (name "unconnected-(U$5-PC6{slash}TIM3_CH1{slash}TIM_CH1{slash}USART6_TX(5T)-Pad37)") (class "Default")
      (node (ref "U$5") (pin "37") (pinfunction "PC6/TIM3_CH1/TIM_CH1/USART6_TX(5T)_37") (pintype "bidirectional"))
    )
    (net (code "123") (name "unconnected-(U$5-PC7{slash}TIM3_CH2{slash}TIM8_CH2{slash}USART6_RX(5T)-Pad38)") (class "Default")
      (node (ref "U$5") (pin "38") (pinfunction "PC7/TIM3_CH2/TIM8_CH2/USART6_RX(5T)_38") (pintype "bidirectional"))
    )
    (net (code "124") (name "unconnected-(U$5-PC10(5T)-Pad51)") (class "Default")
      (node (ref "U$5") (pin "51") (pinfunction "PC10(5T)_51") (pintype "bidirectional"))
    )
    (net (code "125") (name "unconnected-(U$5-PC11(5T)-Pad52)") (class "Default")
      (node (ref "U$5") (pin "52") (pinfunction "PC11(5T)_52") (pintype "bidirectional"))
    )
    (net (code "126") (name "unconnected-(U$5-PD2{slash}TIM3_ETR(5T)-Pad54)") (class "Default")
      (node (ref "U$5") (pin "54") (pinfunction "PD2/TIM3_ETR(5T)_54") (pintype "bidirectional"))
    )
    (net (code "127") (name "unconnected-(U$7-TD-Pad4)") (class "Default")
      (node (ref "U$7") (pin "4") (pinfunction "TD_4") (pintype "bidirectional"))
    )
    (net (code "128") (name "unconnected-(U$18-1.NC(GND)-PadP$1)") (class "Default")
      (node (ref "U$18") (pin "P$1") (pinfunction "1.NC(GND)_P$1") (pintype "bidirectional"))
    )
    (net (code "129") (name "unconnected-(U$18-7.NC-PadP$7)") (class "Default")
      (node (ref "U$18") (pin "P$7") (pinfunction "7.NC_P$7") (pintype "bidirectional"))
    )
    (net (code "130") (name "unconnected-(U$18-30.NC(GND)-PadP$30)") (class "Default")
      (node (ref "U$18") (pin "P$30") (pinfunction "30.NC(GND)_P$30") (pintype "bidirectional"))
    )
  )
)
